# xen_teensy_motherboard_8cv_mki.net
KiCad netlist of a schematic drawn in EAGLE
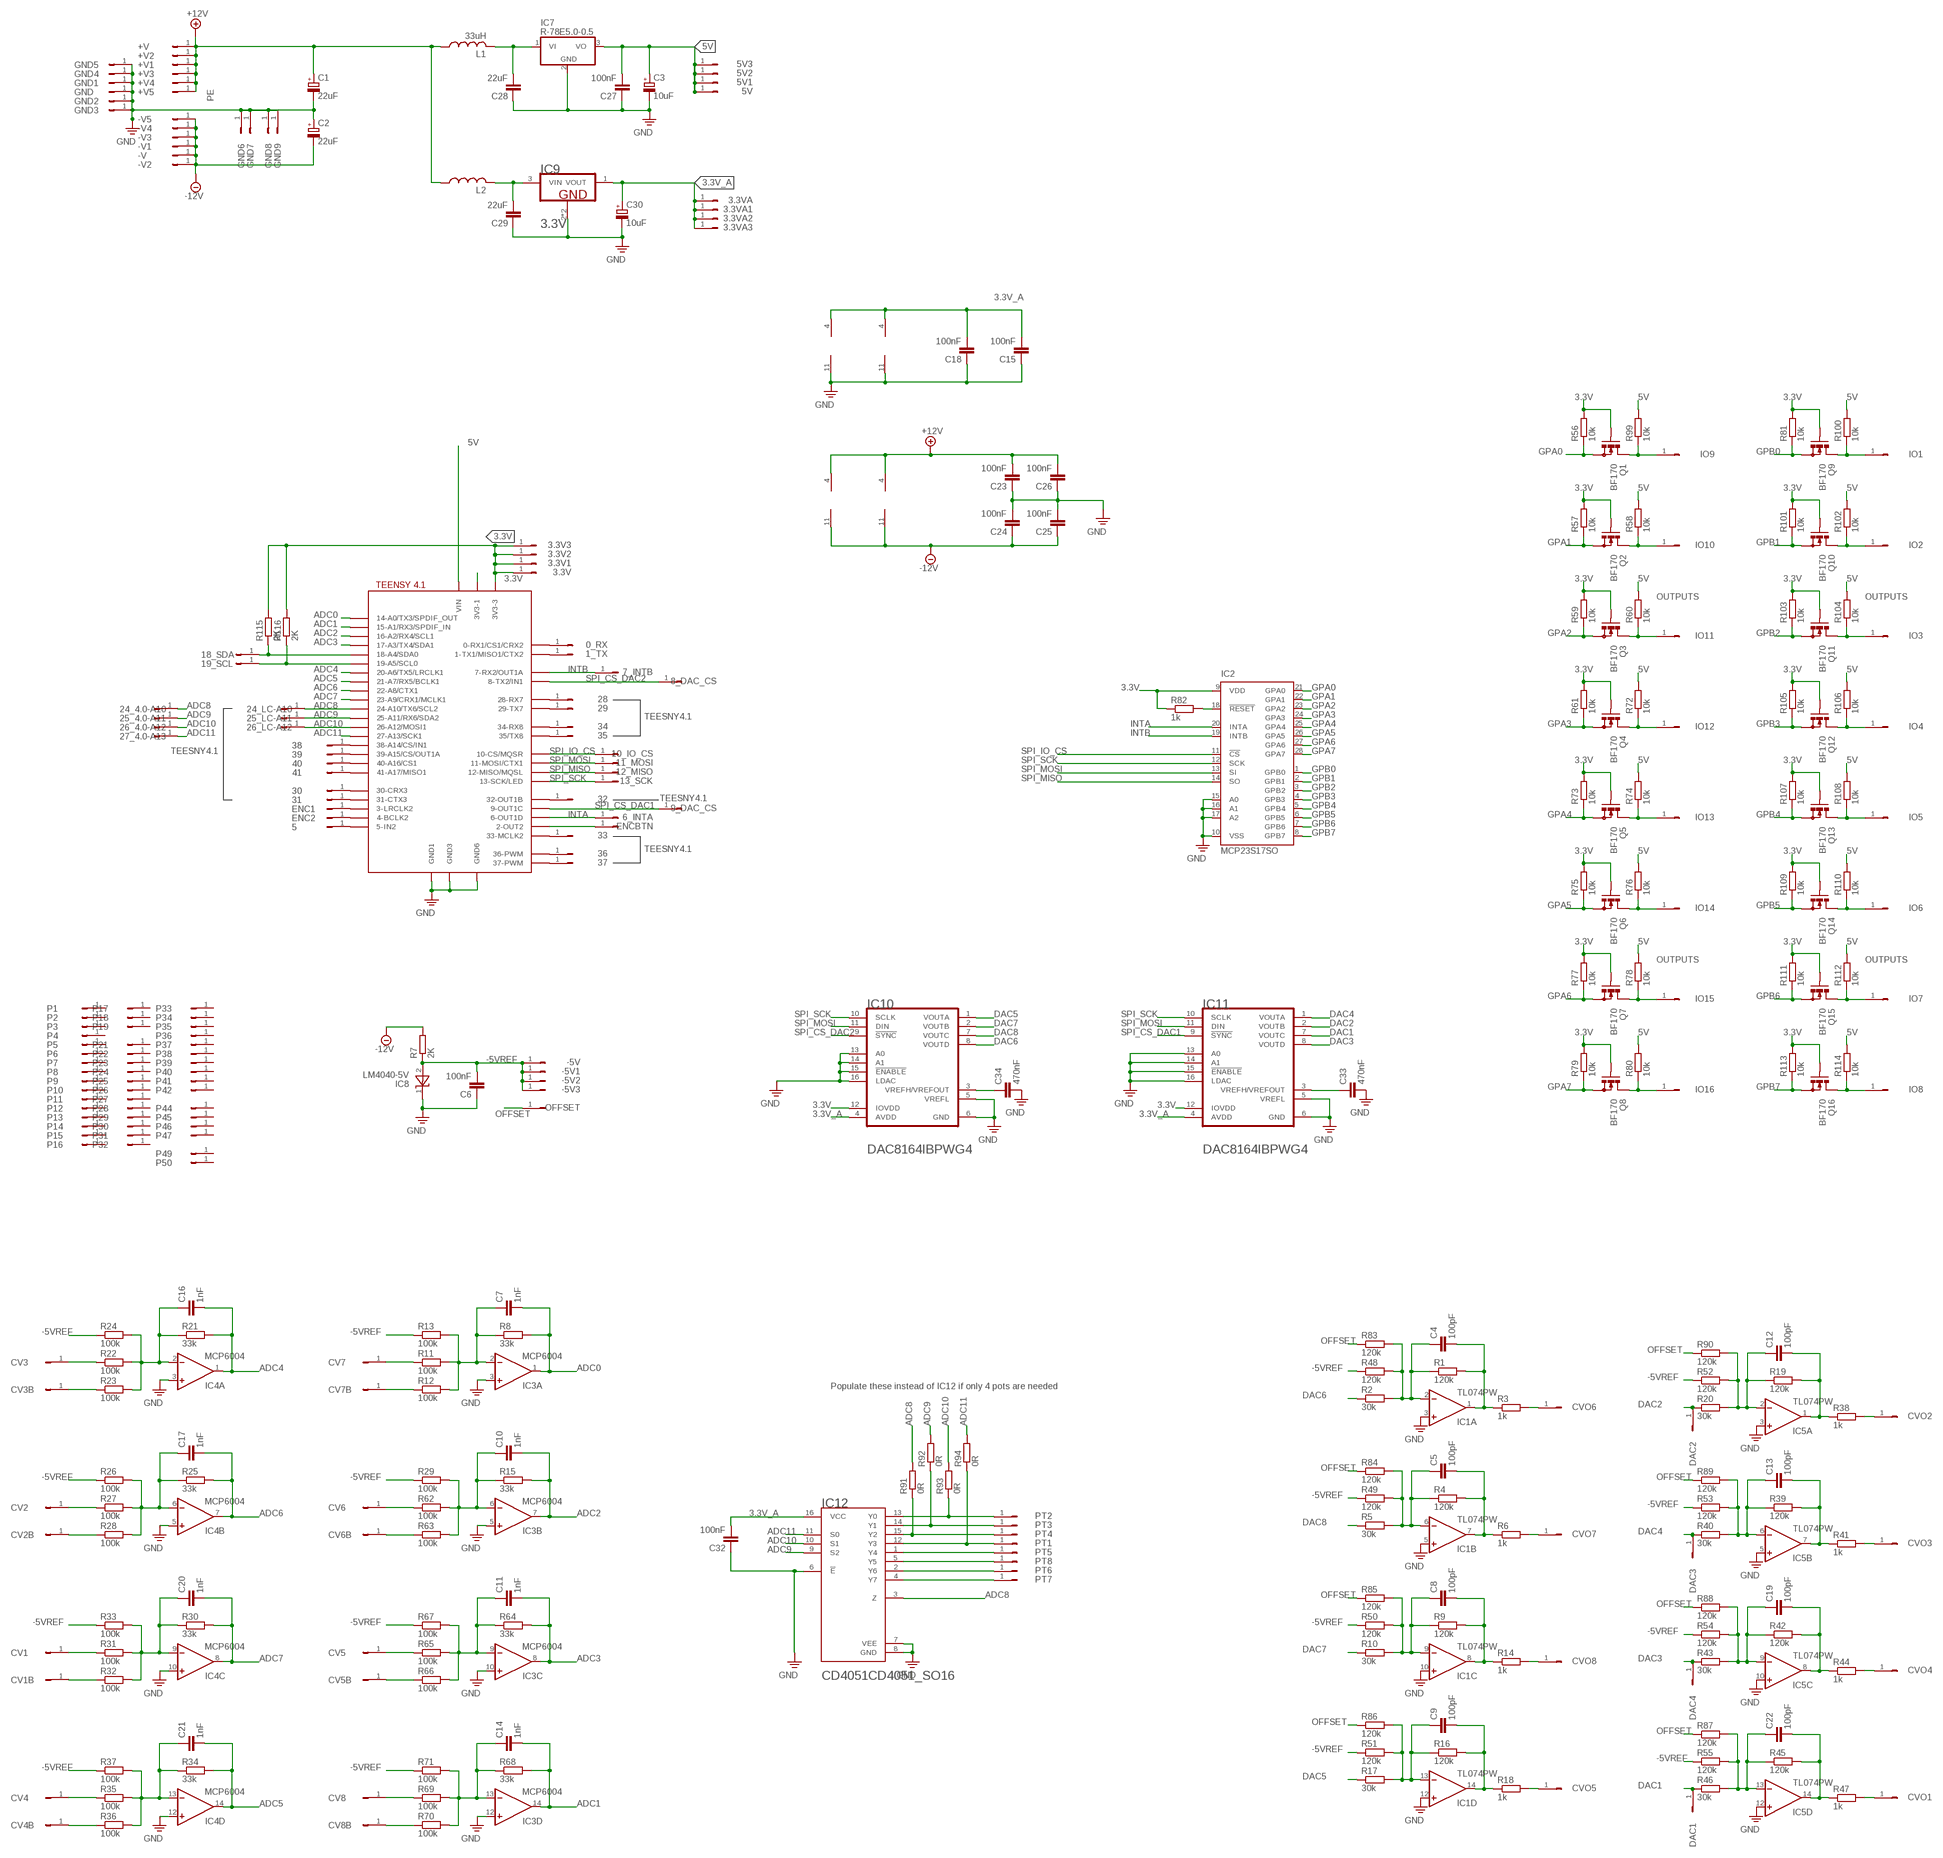
[diagram p0: schematic, sheet 1]

(export (version "E")
  (design (tool "Eeschema 10.0.6"))
  (components
    (comp (ref "+V")
      (value "HEADER/MALE/01")
      (footprint "eagle-import:HEADER_MALE_01")
      (fields (field (name "SPICEPREFIX") "X"))
      (libsource (lib "eagle-import") (part "HEADER/MALE/01"))
    )
    (comp (ref "+V1")
      (value "HEADER/MALE/01")
      (footprint "eagle-import:HEADER_MALE_01")
      (fields (field (name "SPICEPREFIX") "X"))
      (libsource (lib "eagle-import") (part "HEADER/MALE/01"))
    )
    (comp (ref "+V2")
      (value "HEADER/MALE/01")
      (footprint "eagle-import:HEADER_MALE_01")
      (fields (field (name "SPICEPREFIX") "X"))
      (libsource (lib "eagle-import") (part "HEADER/MALE/01"))
    )
    (comp (ref "+V3")
      (value "HEADER/MALE/01")
      (footprint "eagle-import:HEADER_MALE_01")
      (fields (field (name "SPICEPREFIX") "X"))
      (libsource (lib "eagle-import") (part "HEADER/MALE/01"))
    )
    (comp (ref "+V4")
      (value "HEADER/MALE/01")
      (footprint "eagle-import:HEADER_MALE_01")
      (fields (field (name "SPICEPREFIX") "X"))
      (libsource (lib "eagle-import") (part "HEADER/MALE/01"))
    )
    (comp (ref "+V5")
      (value "HEADER/MALE/01")
      (footprint "eagle-import:HEADER_MALE_01")
      (fields (field (name "SPICEPREFIX") "X"))
      (libsource (lib "eagle-import") (part "HEADER/MALE/01"))
    )
    (comp (ref "-5V")
      (value "HEADER/MALE/01")
      (footprint "eagle-import:HEADER_MALE_01")
      (fields (field (name "SPICEPREFIX") "X"))
      (libsource (lib "eagle-import") (part "HEADER/MALE/01"))
    )
    (comp (ref "-5V1")
      (value "HEADER/MALE/01")
      (footprint "eagle-import:HEADER_MALE_01")
      (fields (field (name "SPICEPREFIX") "X"))
      (libsource (lib "eagle-import") (part "HEADER/MALE/01"))
    )
    (comp (ref "-5V2")
      (value "HEADER/MALE/01")
      (footprint "eagle-import:HEADER_MALE_01")
      (fields (field (name "SPICEPREFIX") "X"))
      (libsource (lib "eagle-import") (part "HEADER/MALE/01"))
    )
    (comp (ref "-5V3")
      (value "HEADER/MALE/01")
      (footprint "eagle-import:HEADER_MALE_01")
      (fields (field (name "SPICEPREFIX") "X"))
      (libsource (lib "eagle-import") (part "HEADER/MALE/01"))
    )
    (comp (ref "-V")
      (value "HEADER/MALE/01")
      (footprint "eagle-import:HEADER_MALE_01")
      (fields (field (name "SPICEPREFIX") "X"))
      (libsource (lib "eagle-import") (part "HEADER/MALE/01"))
    )
    (comp (ref "-V1")
      (value "HEADER/MALE/01")
      (footprint "eagle-import:HEADER_MALE_01")
      (fields (field (name "SPICEPREFIX") "X"))
      (libsource (lib "eagle-import") (part "HEADER/MALE/01"))
    )
    (comp (ref "-V2")
      (value "HEADER/MALE/01")
      (footprint "eagle-import:HEADER_MALE_01")
      (fields (field (name "SPICEPREFIX") "X"))
      (libsource (lib "eagle-import") (part "HEADER/MALE/01"))
    )
    (comp (ref "-V3")
      (value "HEADER/MALE/01")
      (footprint "eagle-import:HEADER_MALE_01")
      (fields (field (name "SPICEPREFIX") "X"))
      (libsource (lib "eagle-import") (part "HEADER/MALE/01"))
    )
    (comp (ref "-V4")
      (value "HEADER/MALE/01")
      (footprint "eagle-import:HEADER_MALE_01")
      (fields (field (name "SPICEPREFIX") "X"))
      (libsource (lib "eagle-import") (part "HEADER/MALE/01"))
    )
    (comp (ref "-V5")
      (value "HEADER/MALE/01")
      (footprint "eagle-import:HEADER_MALE_01")
      (fields (field (name "SPICEPREFIX") "X"))
      (libsource (lib "eagle-import") (part "HEADER/MALE/01"))
    )
    (comp (ref "0_RX")
      (value "HEADER/MALE/01")
      (footprint "eagle-import:HEADER_MALE_01")
      (fields (field (name "SPICEPREFIX") "X"))
      (libsource (lib "eagle-import") (part "HEADER/MALE/01"))
    )
    (comp (ref "1_TX")
      (value "HEADER/MALE/01")
      (footprint "eagle-import:HEADER_MALE_01")
      (fields (field (name "SPICEPREFIX") "X"))
      (libsource (lib "eagle-import") (part "HEADER/MALE/01"))
    )
    (comp (ref "3.3V")
      (value "HEADER/MALE/01")
      (footprint "eagle-import:HEADER_MALE_01")
      (fields (field (name "SPICEPREFIX") "X"))
      (libsource (lib "eagle-import") (part "HEADER/MALE/01"))
    )
    (comp (ref "3.3V1")
      (value "HEADER/MALE/01")
      (footprint "eagle-import:HEADER_MALE_01")
      (fields (field (name "SPICEPREFIX") "X"))
      (libsource (lib "eagle-import") (part "HEADER/MALE/01"))
    )
    (comp (ref "3.3V2")
      (value "HEADER/MALE/01")
      (footprint "eagle-import:HEADER_MALE_01")
      (fields (field (name "SPICEPREFIX") "X"))
      (libsource (lib "eagle-import") (part "HEADER/MALE/01"))
    )
    (comp (ref "3.3V3")
      (value "HEADER/MALE/01")
      (footprint "eagle-import:HEADER_MALE_01")
      (fields (field (name "SPICEPREFIX") "X"))
      (libsource (lib "eagle-import") (part "HEADER/MALE/01"))
    )
    (comp (ref "3.3VA")
      (value "HEADER/MALE/01")
      (footprint "eagle-import:HEADER_MALE_01")
      (fields (field (name "SPICEPREFIX") "X"))
      (libsource (lib "eagle-import") (part "HEADER/MALE/01"))
    )
    (comp (ref "3.3VA1")
      (value "HEADER/MALE/01")
      (footprint "eagle-import:HEADER_MALE_01")
      (fields (field (name "SPICEPREFIX") "X"))
      (libsource (lib "eagle-import") (part "HEADER/MALE/01"))
    )
    (comp (ref "3.3VA2")
      (value "HEADER/MALE/01")
      (footprint "eagle-import:HEADER_MALE_01")
      (fields (field (name "SPICEPREFIX") "X"))
      (libsource (lib "eagle-import") (part "HEADER/MALE/01"))
    )
    (comp (ref "3.3VA3")
      (value "HEADER/MALE/01")
      (footprint "eagle-import:HEADER_MALE_01")
      (fields (field (name "SPICEPREFIX") "X"))
      (libsource (lib "eagle-import") (part "HEADER/MALE/01"))
    )
    (comp (ref "5")
      (value "HEADER/MALE/01")
      (footprint "eagle-import:HEADER_MALE_01")
      (fields (field (name "SPICEPREFIX") "X"))
      (libsource (lib "eagle-import") (part "HEADER/MALE/01"))
    )
    (comp (ref "5V")
      (value "HEADER/MALE/01")
      (footprint "eagle-import:HEADER_MALE_01")
      (fields (field (name "SPICEPREFIX") "X"))
      (libsource (lib "eagle-import") (part "HEADER/MALE/01"))
    )
    (comp (ref "5V1")
      (value "HEADER/MALE/01")
      (footprint "eagle-import:HEADER_MALE_01")
      (fields (field (name "SPICEPREFIX") "X"))
      (libsource (lib "eagle-import") (part "HEADER/MALE/01"))
    )
    (comp (ref "5V2")
      (value "HEADER/MALE/01")
      (footprint "eagle-import:HEADER_MALE_01")
      (fields (field (name "SPICEPREFIX") "X"))
      (libsource (lib "eagle-import") (part "HEADER/MALE/01"))
    )
    (comp (ref "5V3")
      (value "HEADER/MALE/01")
      (footprint "eagle-import:HEADER_MALE_01")
      (fields (field (name "SPICEPREFIX") "X"))
      (libsource (lib "eagle-import") (part "HEADER/MALE/01"))
    )
    (comp (ref "6_INTA")
      (value "HEADER/MALE/01")
      (footprint "eagle-import:HEADER_MALE_01")
      (fields (field (name "SPICEPREFIX") "X"))
      (libsource (lib "eagle-import") (part "HEADER/MALE/01"))
    )
    (comp (ref "7_INTB")
      (value "HEADER/MALE/01")
      (footprint "eagle-import:HEADER_MALE_01")
      (fields (field (name "SPICEPREFIX") "X"))
      (libsource (lib "eagle-import") (part "HEADER/MALE/01"))
    )
    (comp (ref "8_DAC_CS")
      (value "HEADER/MALE/01")
      (footprint "eagle-import:HEADER_MALE_01")
      (fields (field (name "SPICEPREFIX") "X"))
      (libsource (lib "eagle-import") (part "HEADER/MALE/01"))
    )
    (comp (ref "9_DAC_CS")
      (value "HEADER/MALE/01")
      (footprint "eagle-import:HEADER_MALE_01")
      (fields (field (name "SPICEPREFIX") "X"))
      (libsource (lib "eagle-import") (part "HEADER/MALE/01"))
    )
    (comp (ref "10_IO_CS")
      (value "HEADER/MALE/01")
      (footprint "eagle-import:HEADER_MALE_01")
      (fields (field (name "SPICEPREFIX") "X"))
      (libsource (lib "eagle-import") (part "HEADER/MALE/01"))
    )
    (comp (ref "11_MOSI")
      (value "HEADER/MALE/01")
      (footprint "eagle-import:HEADER_MALE_01")
      (fields (field (name "SPICEPREFIX") "X"))
      (libsource (lib "eagle-import") (part "HEADER/MALE/01"))
    )
    (comp (ref "12_MISO")
      (value "HEADER/MALE/01")
      (footprint "eagle-import:HEADER_MALE_01")
      (fields (field (name "SPICEPREFIX") "X"))
      (libsource (lib "eagle-import") (part "HEADER/MALE/01"))
    )
    (comp (ref "13_SCK")
      (value "HEADER/MALE/01")
      (footprint "eagle-import:HEADER_MALE_01")
      (fields (field (name "SPICEPREFIX") "X"))
      (libsource (lib "eagle-import") (part "HEADER/MALE/01"))
    )
    (comp (ref "18_SDA")
      (value "HEADER/MALE/01")
      (footprint "eagle-import:HEADER_MALE_01")
      (fields (field (name "SPICEPREFIX") "X"))
      (libsource (lib "eagle-import") (part "HEADER/MALE/01"))
    )
    (comp (ref "19_SCL")
      (value "HEADER/MALE/01")
      (footprint "eagle-import:HEADER_MALE_01")
      (fields (field (name "SPICEPREFIX") "X"))
      (libsource (lib "eagle-import") (part "HEADER/MALE/01"))
    )
    (comp (ref "24_4.0-A10")
      (value "HEADER/MALE/01")
      (footprint "eagle-import:HEADER_MALE_01")
      (fields (field (name "SPICEPREFIX") "X"))
      (libsource (lib "eagle-import") (part "HEADER/MALE/01"))
    )
    (comp (ref "24_LC-A10")
      (value "HEADER/MALE/01")
      (footprint "eagle-import:HEADER_MALE_01")
      (fields (field (name "SPICEPREFIX") "X"))
      (libsource (lib "eagle-import") (part "HEADER/MALE/01"))
    )
    (comp (ref "25_4.0-A11")
      (value "HEADER/MALE/01")
      (footprint "eagle-import:HEADER_MALE_01")
      (fields (field (name "SPICEPREFIX") "X"))
      (libsource (lib "eagle-import") (part "HEADER/MALE/01"))
    )
    (comp (ref "25_LC-A11")
      (value "HEADER/MALE/01")
      (footprint "eagle-import:HEADER_MALE_01")
      (fields (field (name "SPICEPREFIX") "X"))
      (libsource (lib "eagle-import") (part "HEADER/MALE/01"))
    )
    (comp (ref "26_4.0-A12")
      (value "HEADER/MALE/01")
      (footprint "eagle-import:HEADER_MALE_01")
      (fields (field (name "SPICEPREFIX") "X"))
      (libsource (lib "eagle-import") (part "HEADER/MALE/01"))
    )
    (comp (ref "26_LC-A12")
      (value "HEADER/MALE/01")
      (footprint "eagle-import:HEADER_MALE_01")
      (fields (field (name "SPICEPREFIX") "X"))
      (libsource (lib "eagle-import") (part "HEADER/MALE/01"))
    )
    (comp (ref "27_4.0-A13")
      (value "HEADER/MALE/01")
      (footprint "eagle-import:HEADER_MALE_01")
      (fields (field (name "SPICEPREFIX") "X"))
      (libsource (lib "eagle-import") (part "HEADER/MALE/01"))
    )
    (comp (ref "28")
      (value "HEADER/MALE/01")
      (footprint "eagle-import:HEADER_MALE_01")
      (fields (field (name "SPICEPREFIX") "X"))
      (libsource (lib "eagle-import") (part "HEADER/MALE/01"))
    )
    (comp (ref "29")
      (value "HEADER/MALE/01")
      (footprint "eagle-import:HEADER_MALE_01")
      (fields (field (name "SPICEPREFIX") "X"))
      (libsource (lib "eagle-import") (part "HEADER/MALE/01"))
    )
    (comp (ref "30")
      (value "HEADER/MALE/01")
      (footprint "eagle-import:HEADER_MALE_01")
      (fields (field (name "SPICEPREFIX") "X"))
      (libsource (lib "eagle-import") (part "HEADER/MALE/01"))
    )
    (comp (ref "31")
      (value "HEADER/MALE/01")
      (footprint "eagle-import:HEADER_MALE_01")
      (fields (field (name "SPICEPREFIX") "X"))
      (libsource (lib "eagle-import") (part "HEADER/MALE/01"))
    )
    (comp (ref "32")
      (value "HEADER/MALE/01")
      (footprint "eagle-import:HEADER_MALE_01")
      (fields (field (name "SPICEPREFIX") "X"))
      (libsource (lib "eagle-import") (part "HEADER/MALE/01"))
    )
    (comp (ref "33")
      (value "HEADER/MALE/01")
      (footprint "eagle-import:HEADER_MALE_01")
      (fields (field (name "SPICEPREFIX") "X"))
      (libsource (lib "eagle-import") (part "HEADER/MALE/01"))
    )
    (comp (ref "34")
      (value "HEADER/MALE/01")
      (footprint "eagle-import:HEADER_MALE_01")
      (fields (field (name "SPICEPREFIX") "X"))
      (libsource (lib "eagle-import") (part "HEADER/MALE/01"))
    )
    (comp (ref "35")
      (value "HEADER/MALE/01")
      (footprint "eagle-import:HEADER_MALE_01")
      (fields (field (name "SPICEPREFIX") "X"))
      (libsource (lib "eagle-import") (part "HEADER/MALE/01"))
    )
    (comp (ref "36")
      (value "HEADER/MALE/01")
      (footprint "eagle-import:HEADER_MALE_01")
      (fields (field (name "SPICEPREFIX") "X"))
      (libsource (lib "eagle-import") (part "HEADER/MALE/01"))
    )
    (comp (ref "37")
      (value "HEADER/MALE/01")
      (footprint "eagle-import:HEADER_MALE_01")
      (fields (field (name "SPICEPREFIX") "X"))
      (libsource (lib "eagle-import") (part "HEADER/MALE/01"))
    )
    (comp (ref "38")
      (value "HEADER/MALE/01")
      (footprint "eagle-import:HEADER_MALE_01")
      (fields (field (name "SPICEPREFIX") "X"))
      (libsource (lib "eagle-import") (part "HEADER/MALE/01"))
    )
    (comp (ref "39")
      (value "HEADER/MALE/01")
      (footprint "eagle-import:HEADER_MALE_01")
      (fields (field (name "SPICEPREFIX") "X"))
      (libsource (lib "eagle-import") (part "HEADER/MALE/01"))
    )
    (comp (ref "40")
      (value "HEADER/MALE/01")
      (footprint "eagle-import:HEADER_MALE_01")
      (fields (field (name "SPICEPREFIX") "X"))
      (libsource (lib "eagle-import") (part "HEADER/MALE/01"))
    )
    (comp (ref "41")
      (value "HEADER/MALE/01")
      (footprint "eagle-import:HEADER_MALE_01")
      (fields (field (name "SPICEPREFIX") "X"))
      (libsource (lib "eagle-import") (part "HEADER/MALE/01"))
    )
    (comp (ref "C1")
      (value "22uF")
      (footprint "eagle-import:SV-C")
      (fields (field (name "SPICEPREFIX") "C"))
      (libsource (lib "eagle-import") (part "CAPACITOR/POLARIZEDSMDC"))
    )
    (comp (ref "C2")
      (value "22uF")
      (footprint "eagle-import:SV-C")
      (fields (field (name "SPICEPREFIX") "C"))
      (libsource (lib "eagle-import") (part "CAPACITOR/POLARIZEDSMDC"))
    )
    (comp (ref "C3")
      (value "10uF")
      (footprint "eagle-import:SV-B")
      (fields (field (name "SPICEPREFIX") "C"))
      (libsource (lib "eagle-import") (part "CAPACITOR/POLARIZEDSMDB"))
    )
    (comp (ref "C4")
      (value "100pF")
      (footprint "eagle-import:C0603")
      (libsource (lib "eagle-import") (part "CAPACITORC0603"))
    )
    (comp (ref "C5")
      (value "100pF")
      (footprint "eagle-import:C0603")
      (libsource (lib "eagle-import") (part "CAPACITORC0603"))
    )
    (comp (ref "C6")
      (value "100nF")
      (footprint "eagle-import:C0603")
      (libsource (lib "eagle-import") (part "CAPACITORC0603"))
    )
    (comp (ref "C7")
      (value "1nF")
      (footprint "eagle-import:C0603")
      (libsource (lib "eagle-import") (part "CAPACITORC0603"))
    )
    (comp (ref "C8")
      (value "100pF")
      (footprint "eagle-import:C0603")
      (libsource (lib "eagle-import") (part "CAPACITORC0603"))
    )
    (comp (ref "C9")
      (value "100pF")
      (footprint "eagle-import:C0603")
      (libsource (lib "eagle-import") (part "CAPACITORC0603"))
    )
    (comp (ref "C10")
      (value "1nF")
      (footprint "eagle-import:C0603")
      (libsource (lib "eagle-import") (part "CAPACITORC0603"))
    )
    (comp (ref "C11")
      (value "1nF")
      (footprint "eagle-import:C0603")
      (libsource (lib "eagle-import") (part "CAPACITORC0603"))
    )
    (comp (ref "C12")
      (value "100pF")
      (footprint "eagle-import:C0603")
      (libsource (lib "eagle-import") (part "CAPACITORC0603"))
    )
    (comp (ref "C13")
      (value "100pF")
      (footprint "eagle-import:C0603")
      (libsource (lib "eagle-import") (part "CAPACITORC0603"))
    )
    (comp (ref "C14")
      (value "1nF")
      (footprint "eagle-import:C0603")
      (libsource (lib "eagle-import") (part "CAPACITORC0603"))
    )
    (comp (ref "C15")
      (value "100nF")
      (footprint "eagle-import:C0603")
      (libsource (lib "eagle-import") (part "CAPACITORC0603"))
    )
    (comp (ref "C16")
      (value "1nF")
      (footprint "eagle-import:C0603")
      (libsource (lib "eagle-import") (part "CAPACITORC0603"))
    )
    (comp (ref "C17")
      (value "1nF")
      (footprint "eagle-import:C0603")
      (libsource (lib "eagle-import") (part "CAPACITORC0603"))
    )
    (comp (ref "C18")
      (value "100nF")
      (footprint "eagle-import:C0603")
      (libsource (lib "eagle-import") (part "CAPACITORC0603"))
    )
    (comp (ref "C19")
      (value "100pF")
      (footprint "eagle-import:C0603")
      (libsource (lib "eagle-import") (part "CAPACITORC0603"))
    )
    (comp (ref "C20")
      (value "1nF")
      (footprint "eagle-import:C0603")
      (libsource (lib "eagle-import") (part "CAPACITORC0603"))
    )
    (comp (ref "C21")
      (value "1nF")
      (footprint "eagle-import:C0603")
      (libsource (lib "eagle-import") (part "CAPACITORC0603"))
    )
    (comp (ref "C22")
      (value "100pF")
      (footprint "eagle-import:C0603")
      (libsource (lib "eagle-import") (part "CAPACITORC0603"))
    )
    (comp (ref "C23")
      (value "100nF")
      (footprint "eagle-import:C0603")
      (libsource (lib "eagle-import") (part "CAPACITORC0603"))
    )
    (comp (ref "C24")
      (value "100nF")
      (footprint "eagle-import:C0603")
      (libsource (lib "eagle-import") (part "CAPACITORC0603"))
    )
    (comp (ref "C25")
      (value "100nF")
      (footprint "eagle-import:C0603")
      (libsource (lib "eagle-import") (part "CAPACITORC0603"))
    )
    (comp (ref "C26")
      (value "100nF")
      (footprint "eagle-import:C0603")
      (libsource (lib "eagle-import") (part "CAPACITORC0603"))
    )
    (comp (ref "C27")
      (value "100nF")
      (footprint "eagle-import:C0603")
      (libsource (lib "eagle-import") (part "CAPACITORC0603"))
    )
    (comp (ref "C28")
      (value "22uF")
      (footprint "eagle-import:C0805")
      (libsource (lib "eagle-import") (part "CAPACITORC0805"))
    )
    (comp (ref "C29")
      (value "22uF")
      (footprint "eagle-import:C0805")
      (libsource (lib "eagle-import") (part "CAPACITORC0805"))
    )
    (comp (ref "C30")
      (value "10uF")
      (footprint "eagle-import:SV-B")
      (fields (field (name "SPICEPREFIX") "C"))
      (libsource (lib "eagle-import") (part "CAPACITOR/POLARIZEDSMDB"))
    )
    (comp (ref "C32")
      (value "100nF")
      (footprint "eagle-import:C0603")
      (libsource (lib "eagle-import") (part "CAPACITORC0603"))
    )
    (comp (ref "C33")
      (value "470nF")
      (footprint "eagle-import:C0603")
      (libsource (lib "eagle-import") (part "CAPACITORC0603"))
    )
    (comp (ref "C34")
      (value "470nF")
      (footprint "eagle-import:C0603")
      (libsource (lib "eagle-import") (part "CAPACITORC0603"))
    )
    (comp (ref "CV1")
      (value "HEADER/MALE/01")
      (footprint "eagle-import:HEADER_MALE_01")
      (fields (field (name "SPICEPREFIX") "X"))
      (libsource (lib "eagle-import") (part "HEADER/MALE/01"))
    )
    (comp (ref "CV1B")
      (value "HEADER/MALE/01")
      (footprint "eagle-import:HEADER_MALE_01")
      (fields (field (name "SPICEPREFIX") "X"))
      (libsource (lib "eagle-import") (part "HEADER/MALE/01"))
    )
    (comp (ref "CV2")
      (value "HEADER/MALE/01")
      (footprint "eagle-import:HEADER_MALE_01")
      (fields (field (name "SPICEPREFIX") "X"))
      (libsource (lib "eagle-import") (part "HEADER/MALE/01"))
    )
    (comp (ref "CV2B")
      (value "HEADER/MALE/01")
      (footprint "eagle-import:HEADER_MALE_01")
      (fields (field (name "SPICEPREFIX") "X"))
      (libsource (lib "eagle-import") (part "HEADER/MALE/01"))
    )
    (comp (ref "CV3")
      (value "HEADER/MALE/01")
      (footprint "eagle-import:HEADER_MALE_01")
      (fields (field (name "SPICEPREFIX") "X"))
      (libsource (lib "eagle-import") (part "HEADER/MALE/01"))
    )
    (comp (ref "CV3B")
      (value "HEADER/MALE/01")
      (footprint "eagle-import:HEADER_MALE_01")
      (fields (field (name "SPICEPREFIX") "X"))
      (libsource (lib "eagle-import") (part "HEADER/MALE/01"))
    )
    (comp (ref "CV4")
      (value "HEADER/MALE/01")
      (footprint "eagle-import:HEADER_MALE_01")
      (fields (field (name "SPICEPREFIX") "X"))
      (libsource (lib "eagle-import") (part "HEADER/MALE/01"))
    )
    (comp (ref "CV4B")
      (value "HEADER/MALE/01")
      (footprint "eagle-import:HEADER_MALE_01")
      (fields (field (name "SPICEPREFIX") "X"))
      (libsource (lib "eagle-import") (part "HEADER/MALE/01"))
    )
    (comp (ref "CV5")
      (value "HEADER/MALE/01")
      (footprint "eagle-import:HEADER_MALE_01")
      (fields (field (name "SPICEPREFIX") "X"))
      (libsource (lib "eagle-import") (part "HEADER/MALE/01"))
    )
    (comp (ref "CV5B")
      (value "HEADER/MALE/01")
      (footprint "eagle-import:HEADER_MALE_01")
      (fields (field (name "SPICEPREFIX") "X"))
      (libsource (lib "eagle-import") (part "HEADER/MALE/01"))
    )
    (comp (ref "CV6")
      (value "HEADER/MALE/01")
      (footprint "eagle-import:HEADER_MALE_01")
      (fields (field (name "SPICEPREFIX") "X"))
      (libsource (lib "eagle-import") (part "HEADER/MALE/01"))
    )
    (comp (ref "CV6B")
      (value "HEADER/MALE/01")
      (footprint "eagle-import:HEADER_MALE_01")
      (fields (field (name "SPICEPREFIX") "X"))
      (libsource (lib "eagle-import") (part "HEADER/MALE/01"))
    )
    (comp (ref "CV7")
      (value "HEADER/MALE/01")
      (footprint "eagle-import:HEADER_MALE_01")
      (fields (field (name "SPICEPREFIX") "X"))
      (libsource (lib "eagle-import") (part "HEADER/MALE/01"))
    )
    (comp (ref "CV7B")
      (value "HEADER/MALE/01")
      (footprint "eagle-import:HEADER_MALE_01")
      (fields (field (name "SPICEPREFIX") "X"))
      (libsource (lib "eagle-import") (part "HEADER/MALE/01"))
    )
    (comp (ref "CV8")
      (value "HEADER/MALE/01")
      (footprint "eagle-import:HEADER_MALE_01")
      (fields (field (name "SPICEPREFIX") "X"))
      (libsource (lib "eagle-import") (part "HEADER/MALE/01"))
    )
    (comp (ref "CV8B")
      (value "HEADER/MALE/01")
      (footprint "eagle-import:HEADER_MALE_01")
      (fields (field (name "SPICEPREFIX") "X"))
      (libsource (lib "eagle-import") (part "HEADER/MALE/01"))
    )
    (comp (ref "CVO1")
      (value "HEADER/MALE/01")
      (footprint "eagle-import:HEADER_MALE_01")
      (fields (field (name "SPICEPREFIX") "X"))
      (libsource (lib "eagle-import") (part "HEADER/MALE/01"))
    )
    (comp (ref "CVO2")
      (value "HEADER/MALE/01")
      (footprint "eagle-import:HEADER_MALE_01")
      (fields (field (name "SPICEPREFIX") "X"))
      (libsource (lib "eagle-import") (part "HEADER/MALE/01"))
    )
    (comp (ref "CVO3")
      (value "HEADER/MALE/01")
      (footprint "eagle-import:HEADER_MALE_01")
      (fields (field (name "SPICEPREFIX") "X"))
      (libsource (lib "eagle-import") (part "HEADER/MALE/01"))
    )
    (comp (ref "CVO4")
      (value "HEADER/MALE/01")
      (footprint "eagle-import:HEADER_MALE_01")
      (fields (field (name "SPICEPREFIX") "X"))
      (libsource (lib "eagle-import") (part "HEADER/MALE/01"))
    )
    (comp (ref "CVO5")
      (value "HEADER/MALE/01")
      (footprint "eagle-import:HEADER_MALE_01")
      (fields (field (name "SPICEPREFIX") "X"))
      (libsource (lib "eagle-import") (part "HEADER/MALE/01"))
    )
    (comp (ref "CVO6")
      (value "HEADER/MALE/01")
      (footprint "eagle-import:HEADER_MALE_01")
      (fields (field (name "SPICEPREFIX") "X"))
      (libsource (lib "eagle-import") (part "HEADER/MALE/01"))
    )
    (comp (ref "CVO7")
      (value "HEADER/MALE/01")
      (footprint "eagle-import:HEADER_MALE_01")
      (fields (field (name "SPICEPREFIX") "X"))
      (libsource (lib "eagle-import") (part "HEADER/MALE/01"))
    )
    (comp (ref "CVO8")
      (value "HEADER/MALE/01")
      (footprint "eagle-import:HEADER_MALE_01")
      (fields (field (name "SPICEPREFIX") "X"))
      (libsource (lib "eagle-import") (part "HEADER/MALE/01"))
    )
    (comp (ref "DAC1")
      (value "HEADER/MALE/01")
      (footprint "eagle-import:HEADER_MALE_01")
      (fields (field (name "SPICEPREFIX") "X"))
      (libsource (lib "eagle-import") (part "HEADER/MALE/01"))
    )
    (comp (ref "DAC2")
      (value "HEADER/MALE/01")
      (footprint "eagle-import:HEADER_MALE_01")
      (fields (field (name "SPICEPREFIX") "X"))
      (libsource (lib "eagle-import") (part "HEADER/MALE/01"))
    )
    (comp (ref "DAC3")
      (value "HEADER/MALE/01")
      (footprint "eagle-import:HEADER_MALE_01")
      (fields (field (name "SPICEPREFIX") "X"))
      (libsource (lib "eagle-import") (part "HEADER/MALE/01"))
    )
    (comp (ref "DAC4")
      (value "HEADER/MALE/01")
      (footprint "eagle-import:HEADER_MALE_01")
      (fields (field (name "SPICEPREFIX") "X"))
      (libsource (lib "eagle-import") (part "HEADER/MALE/01"))
    )
    (comp (ref "ENC1")
      (value "HEADER/MALE/01")
      (footprint "eagle-import:HEADER_MALE_01")
      (fields (field (name "SPICEPREFIX") "X"))
      (libsource (lib "eagle-import") (part "HEADER/MALE/01"))
    )
    (comp (ref "ENC2")
      (value "HEADER/MALE/01")
      (footprint "eagle-import:HEADER_MALE_01")
      (fields (field (name "SPICEPREFIX") "X"))
      (libsource (lib "eagle-import") (part "HEADER/MALE/01"))
    )
    (comp (ref "ENCBTN")
      (value "HEADER/MALE/01")
      (footprint "eagle-import:HEADER_MALE_01")
      (fields (field (name "SPICEPREFIX") "X"))
      (libsource (lib "eagle-import") (part "HEADER/MALE/01"))
    )
    (comp (ref "GND")
      (value "HEADER/MALE/01")
      (footprint "eagle-import:HEADER_MALE_01")
      (fields (field (name "SPICEPREFIX") "X"))
      (libsource (lib "eagle-import") (part "HEADER/MALE/01"))
    )
    (comp (ref "GND1")
      (value "HEADER/MALE/01")
      (footprint "eagle-import:HEADER_MALE_01")
      (fields (field (name "SPICEPREFIX") "X"))
      (libsource (lib "eagle-import") (part "HEADER/MALE/01"))
    )
    (comp (ref "GND2")
      (value "HEADER/MALE/01")
      (footprint "eagle-import:HEADER_MALE_01")
      (fields (field (name "SPICEPREFIX") "X"))
      (libsource (lib "eagle-import") (part "HEADER/MALE/01"))
    )
    (comp (ref "GND3")
      (value "HEADER/MALE/01")
      (footprint "eagle-import:HEADER_MALE_01")
      (fields (field (name "SPICEPREFIX") "X"))
      (libsource (lib "eagle-import") (part "HEADER/MALE/01"))
    )
    (comp (ref "GND4")
      (value "HEADER/MALE/01")
      (footprint "eagle-import:HEADER_MALE_01")
      (fields (field (name "SPICEPREFIX") "X"))
      (libsource (lib "eagle-import") (part "HEADER/MALE/01"))
    )
    (comp (ref "GND5")
      (value "HEADER/MALE/01")
      (footprint "eagle-import:HEADER_MALE_01")
      (fields (field (name "SPICEPREFIX") "X"))
      (libsource (lib "eagle-import") (part "HEADER/MALE/01"))
    )
    (comp (ref "GND6")
      (value "HEADER/MALE/01")
      (footprint "eagle-import:HEADER_MALE_01")
      (fields (field (name "SPICEPREFIX") "X"))
      (libsource (lib "eagle-import") (part "HEADER/MALE/01"))
    )
    (comp (ref "GND7")
      (value "HEADER/MALE/01")
      (footprint "eagle-import:HEADER_MALE_01")
      (fields (field (name "SPICEPREFIX") "X"))
      (libsource (lib "eagle-import") (part "HEADER/MALE/01"))
    )
    (comp (ref "GND8")
      (value "HEADER/MALE/01")
      (footprint "eagle-import:HEADER_MALE_01")
      (fields (field (name "SPICEPREFIX") "X"))
      (libsource (lib "eagle-import") (part "HEADER/MALE/01"))
    )
    (comp (ref "GND9")
      (value "HEADER/MALE/01")
      (footprint "eagle-import:HEADER_MALE_01")
      (fields (field (name "SPICEPREFIX") "X"))
      (libsource (lib "eagle-import") (part "HEADER/MALE/01"))
    )
    (comp (ref "IC1")
      (value "TL074PW")
      (footprint "eagle-import:TSSOP14")
      (libsource (lib "eagle-import") (part "TL074PW"))
    )
    (comp (ref "IC2")
      (value "MCP23S17SO")
      (footprint "eagle-import:SO28W")
      (fields (field (name "MF") "MICROCHIP") (field (name "MPN") "MCP23S17-E/SO"))
      (libsource (lib "eagle-import") (part "MCP23S17SO"))
    )
    (comp (ref "IC3")
      (value "MCP6004")
      (footprint "eagle-import:TSSOP14")
      (libsource (lib "eagle-import") (part "TL074PW"))
    )
    (comp (ref "IC4")
      (value "MCP6004")
      (footprint "eagle-import:TSSOP14")
      (libsource (lib "eagle-import") (part "TL074PW"))
    )
    (comp (ref "IC5")
      (value "TL074PW")
      (footprint "eagle-import:TSSOP14")
      (libsource (lib "eagle-import") (part "TL074PW"))
    )
    (comp (ref "IC6")
      (value "TEENSY41-OUTER")
      (footprint "eagle-import:TENNSY41-OUTER")
      (libsource (lib "eagle-import") (part "TEENSY41-OUTER"))
    )
    (comp (ref "IC7")
      (value "R-78E5.0-0.5")
      (footprint "eagle-import:WE78")
      (libsource (lib "eagle-import") (part "WE173950378"))
    )
    (comp (ref "IC8")
      (value "LM4040-5V")
      (footprint "eagle-import:SOT-23")
      (libsource (lib "eagle-import") (part "LM4040CYM3-2.5"))
    )
    (comp (ref "IC9")
      (value "3.3V")
      (footprint "eagle-import:LD2981-SOT89")
      (fields (field (name "MF") "STMicroelectronics") (field (name "MPN") "LD2981CU33TR"))
      (libsource (lib "eagle-import") (part "LD2981LD2981-SOT89"))
    )
    (comp (ref "IC10")
      (value "TEXAS_INSTRUMENTS_DAC8164IBPWG4TEXAS_INSTRUMENTS_DAC8164IBPWG4_0_1")
      (footprint "eagle-import:TEXAS_INSTRUMENTS_DAC8164IBPWG4_1")
      (fields (field (name "MF") "Texas Instruments") (field (name "MPN") "DAC8164IBPWG4"))
      (libsource (lib "eagle-import") (part "TEXAS_INSTRUMENTS_DAC8164IBPWG4TEXAS_INSTRUMENTS_DAC8164IBPWG4_0_1"))
    )
    (comp (ref "IC11")
      (value "TEXAS_INSTRUMENTS_DAC8164IBPWG4TEXAS_INSTRUMENTS_DAC8164IBPWG4_0_1")
      (footprint "eagle-import:TEXAS_INSTRUMENTS_DAC8164IBPWG4_1")
      (fields (field (name "MF") "Texas Instruments") (field (name "MPN") "DAC8164IBPWG4"))
      (libsource (lib "eagle-import") (part "TEXAS_INSTRUMENTS_DAC8164IBPWG4TEXAS_INSTRUMENTS_DAC8164IBPWG4_0_1"))
    )
    (comp (ref "IC12")
      (value "CD4051CD4051_SO16")
      (footprint "eagle-import:SO16")
      (libsource (lib "eagle-import") (part "CD4051CD4051_SO16"))
    )
    (comp (ref "IO1")
      (value "HEADER/MALE/01")
      (footprint "eagle-import:HEADER_MALE_01")
      (fields (field (name "SPICEPREFIX") "X"))
      (libsource (lib "eagle-import") (part "HEADER/MALE/01"))
    )
    (comp (ref "IO2")
      (value "HEADER/MALE/01")
      (footprint "eagle-import:HEADER_MALE_01")
      (fields (field (name "SPICEPREFIX") "X"))
      (libsource (lib "eagle-import") (part "HEADER/MALE/01"))
    )
    (comp (ref "IO3")
      (value "HEADER/MALE/01")
      (footprint "eagle-import:HEADER_MALE_01")
      (fields (field (name "SPICEPREFIX") "X"))
      (libsource (lib "eagle-import") (part "HEADER/MALE/01"))
    )
    (comp (ref "IO4")
      (value "HEADER/MALE/01")
      (footprint "eagle-import:HEADER_MALE_01")
      (fields (field (name "SPICEPREFIX") "X"))
      (libsource (lib "eagle-import") (part "HEADER/MALE/01"))
    )
    (comp (ref "IO5")
      (value "HEADER/MALE/01")
      (footprint "eagle-import:HEADER_MALE_01")
      (fields (field (name "SPICEPREFIX") "X"))
      (libsource (lib "eagle-import") (part "HEADER/MALE/01"))
    )
    (comp (ref "IO6")
      (value "HEADER/MALE/01")
      (footprint "eagle-import:HEADER_MALE_01")
      (fields (field (name "SPICEPREFIX") "X"))
      (libsource (lib "eagle-import") (part "HEADER/MALE/01"))
    )
    (comp (ref "IO7")
      (value "HEADER/MALE/01")
      (footprint "eagle-import:HEADER_MALE_01")
      (fields (field (name "SPICEPREFIX") "X"))
      (libsource (lib "eagle-import") (part "HEADER/MALE/01"))
    )
    (comp (ref "IO8")
      (value "HEADER/MALE/01")
      (footprint "eagle-import:HEADER_MALE_01")
      (fields (field (name "SPICEPREFIX") "X"))
      (libsource (lib "eagle-import") (part "HEADER/MALE/01"))
    )
    (comp (ref "IO9")
      (value "HEADER/MALE/01")
      (footprint "eagle-import:HEADER_MALE_01")
      (fields (field (name "SPICEPREFIX") "X"))
      (libsource (lib "eagle-import") (part "HEADER/MALE/01"))
    )
    (comp (ref "IO10")
      (value "HEADER/MALE/01")
      (footprint "eagle-import:HEADER_MALE_01")
      (fields (field (name "SPICEPREFIX") "X"))
      (libsource (lib "eagle-import") (part "HEADER/MALE/01"))
    )
    (comp (ref "IO11")
      (value "HEADER/MALE/01")
      (footprint "eagle-import:HEADER_MALE_01")
      (fields (field (name "SPICEPREFIX") "X"))
      (libsource (lib "eagle-import") (part "HEADER/MALE/01"))
    )
    (comp (ref "IO12")
      (value "HEADER/MALE/01")
      (footprint "eagle-import:HEADER_MALE_01")
      (fields (field (name "SPICEPREFIX") "X"))
      (libsource (lib "eagle-import") (part "HEADER/MALE/01"))
    )
    (comp (ref "IO13")
      (value "HEADER/MALE/01")
      (footprint "eagle-import:HEADER_MALE_01")
      (fields (field (name "SPICEPREFIX") "X"))
      (libsource (lib "eagle-import") (part "HEADER/MALE/01"))
    )
    (comp (ref "IO14")
      (value "HEADER/MALE/01")
      (footprint "eagle-import:HEADER_MALE_01")
      (fields (field (name "SPICEPREFIX") "X"))
      (libsource (lib "eagle-import") (part "HEADER/MALE/01"))
    )
    (comp (ref "IO15")
      (value "HEADER/MALE/01")
      (footprint "eagle-import:HEADER_MALE_01")
      (fields (field (name "SPICEPREFIX") "X"))
      (libsource (lib "eagle-import") (part "HEADER/MALE/01"))
    )
    (comp (ref "IO16")
      (value "HEADER/MALE/01")
      (footprint "eagle-import:HEADER_MALE_01")
      (fields (field (name "SPICEPREFIX") "X"))
      (libsource (lib "eagle-import") (part "HEADER/MALE/01"))
    )
    (comp (ref "L1")
      (value "33uH")
      (footprint "eagle-import:L2012C")
      (libsource (lib "eagle-import") (part "INDUCTORL2012C"))
    )
    (comp (ref "L2")
      (value "INDUCTORL0603")
      (footprint "eagle-import:R0603")
      (libsource (lib "eagle-import") (part "INDUCTORL0603"))
    )
    (comp (ref "OFFSET")
      (value "HEADER/MALE/01")
      (footprint "eagle-import:HEADER_MALE_01")
      (fields (field (name "SPICEPREFIX") "X"))
      (libsource (lib "eagle-import") (part "HEADER/MALE/01"))
    )
    (comp (ref "P1")
      (value "HEADER/MALE/01NOBORDER")
      (footprint "eagle-import:HEADER_MALE_01_NOBORDER")
      (fields (field (name "SPICEPREFIX") "X"))
      (libsource (lib "eagle-import") (part "HEADER/MALE/01NOBORDER"))
    )
    (comp (ref "P2")
      (value "HEADER/MALE/01NOBORDER")
      (footprint "eagle-import:HEADER_MALE_01_NOBORDER")
      (fields (field (name "SPICEPREFIX") "X"))
      (libsource (lib "eagle-import") (part "HEADER/MALE/01NOBORDER"))
    )
    (comp (ref "P3")
      (value "HEADER/MALE/01NOBORDER")
      (footprint "eagle-import:HEADER_MALE_01_NOBORDER")
      (fields (field (name "SPICEPREFIX") "X"))
      (libsource (lib "eagle-import") (part "HEADER/MALE/01NOBORDER"))
    )
    (comp (ref "P4")
      (value "HEADER/MALE/01NOBORDER")
      (footprint "eagle-import:HEADER_MALE_01_NOBORDER")
      (fields (field (name "SPICEPREFIX") "X"))
      (libsource (lib "eagle-import") (part "HEADER/MALE/01NOBORDER"))
    )
    (comp (ref "P5")
      (value "HEADER/MALE/01NOBORDER")
      (footprint "eagle-import:HEADER_MALE_01_NOBORDER")
      (fields (field (name "SPICEPREFIX") "X"))
      (libsource (lib "eagle-import") (part "HEADER/MALE/01NOBORDER"))
    )
    (comp (ref "P6")
      (value "HEADER/MALE/01NOBORDER")
      (footprint "eagle-import:HEADER_MALE_01_NOBORDER")
      (fields (field (name "SPICEPREFIX") "X"))
      (libsource (lib "eagle-import") (part "HEADER/MALE/01NOBORDER"))
    )
    (comp (ref "P7")
      (value "HEADER/MALE/01NOBORDER")
      (footprint "eagle-import:HEADER_MALE_01_NOBORDER")
      (fields (field (name "SPICEPREFIX") "X"))
      (libsource (lib "eagle-import") (part "HEADER/MALE/01NOBORDER"))
    )
    (comp (ref "P8")
      (value "HEADER/MALE/01NOBORDER")
      (footprint "eagle-import:HEADER_MALE_01_NOBORDER")
      (fields (field (name "SPICEPREFIX") "X"))
      (libsource (lib "eagle-import") (part "HEADER/MALE/01NOBORDER"))
    )
    (comp (ref "P9")
      (value "HEADER/MALE/01NOBORDER")
      (footprint "eagle-import:HEADER_MALE_01_NOBORDER")
      (fields (field (name "SPICEPREFIX") "X"))
      (libsource (lib "eagle-import") (part "HEADER/MALE/01NOBORDER"))
    )
    (comp (ref "P10")
      (value "HEADER/MALE/01NOBORDER")
      (footprint "eagle-import:HEADER_MALE_01_NOBORDER")
      (fields (field (name "SPICEPREFIX") "X"))
      (libsource (lib "eagle-import") (part "HEADER/MALE/01NOBORDER"))
    )
    (comp (ref "P11")
      (value "HEADER/MALE/01NOBORDER")
      (footprint "eagle-import:HEADER_MALE_01_NOBORDER")
      (fields (field (name "SPICEPREFIX") "X"))
      (libsource (lib "eagle-import") (part "HEADER/MALE/01NOBORDER"))
    )
    (comp (ref "P12")
      (value "HEADER/MALE/01NOBORDER")
      (footprint "eagle-import:HEADER_MALE_01_NOBORDER")
      (fields (field (name "SPICEPREFIX") "X"))
      (libsource (lib "eagle-import") (part "HEADER/MALE/01NOBORDER"))
    )
    (comp (ref "P13")
      (value "HEADER/MALE/01NOBORDER")
      (footprint "eagle-import:HEADER_MALE_01_NOBORDER")
      (fields (field (name "SPICEPREFIX") "X"))
      (libsource (lib "eagle-import") (part "HEADER/MALE/01NOBORDER"))
    )
    (comp (ref "P14")
      (value "HEADER/MALE/01NOBORDER")
      (footprint "eagle-import:HEADER_MALE_01_NOBORDER")
      (fields (field (name "SPICEPREFIX") "X"))
      (libsource (lib "eagle-import") (part "HEADER/MALE/01NOBORDER"))
    )
    (comp (ref "P15")
      (value "HEADER/MALE/01NOBORDER")
      (footprint "eagle-import:HEADER_MALE_01_NOBORDER")
      (fields (field (name "SPICEPREFIX") "X"))
      (libsource (lib "eagle-import") (part "HEADER/MALE/01NOBORDER"))
    )
    (comp (ref "P16")
      (value "HEADER/MALE/01NOBORDER")
      (footprint "eagle-import:HEADER_MALE_01_NOBORDER")
      (fields (field (name "SPICEPREFIX") "X"))
      (libsource (lib "eagle-import") (part "HEADER/MALE/01NOBORDER"))
    )
    (comp (ref "P17")
      (value "HEADER/MALE/01NOBORDER")
      (footprint "eagle-import:HEADER_MALE_01_NOBORDER")
      (fields (field (name "SPICEPREFIX") "X"))
      (libsource (lib "eagle-import") (part "HEADER/MALE/01NOBORDER"))
    )
    (comp (ref "P18")
      (value "HEADER/MALE/01NOBORDER")
      (footprint "eagle-import:HEADER_MALE_01_NOBORDER")
      (fields (field (name "SPICEPREFIX") "X"))
      (libsource (lib "eagle-import") (part "HEADER/MALE/01NOBORDER"))
    )
    (comp (ref "P19")
      (value "HEADER/MALE/01NOBORDER")
      (footprint "eagle-import:HEADER_MALE_01_NOBORDER")
      (fields (field (name "SPICEPREFIX") "X"))
      (libsource (lib "eagle-import") (part "HEADER/MALE/01NOBORDER"))
    )
    (comp (ref "P21")
      (value "HEADER/MALE/01NOBORDER")
      (footprint "eagle-import:HEADER_MALE_01_NOBORDER")
      (fields (field (name "SPICEPREFIX") "X"))
      (libsource (lib "eagle-import") (part "HEADER/MALE/01NOBORDER"))
    )
    (comp (ref "P22")
      (value "HEADER/MALE/01NOBORDER")
      (footprint "eagle-import:HEADER_MALE_01_NOBORDER")
      (fields (field (name "SPICEPREFIX") "X"))
      (libsource (lib "eagle-import") (part "HEADER/MALE/01NOBORDER"))
    )
    (comp (ref "P23")
      (value "HEADER/MALE/01NOBORDER")
      (footprint "eagle-import:HEADER_MALE_01_NOBORDER")
      (fields (field (name "SPICEPREFIX") "X"))
      (libsource (lib "eagle-import") (part "HEADER/MALE/01NOBORDER"))
    )
    (comp (ref "P24")
      (value "HEADER/MALE/01NOBORDER")
      (footprint "eagle-import:HEADER_MALE_01_NOBORDER")
      (fields (field (name "SPICEPREFIX") "X"))
      (libsource (lib "eagle-import") (part "HEADER/MALE/01NOBORDER"))
    )
    (comp (ref "P25")
      (value "HEADER/MALE/01NOBORDER")
      (footprint "eagle-import:HEADER_MALE_01_NOBORDER")
      (fields (field (name "SPICEPREFIX") "X"))
      (libsource (lib "eagle-import") (part "HEADER/MALE/01NOBORDER"))
    )
    (comp (ref "P26")
      (value "HEADER/MALE/01NOBORDER")
      (footprint "eagle-import:HEADER_MALE_01_NOBORDER")
      (fields (field (name "SPICEPREFIX") "X"))
      (libsource (lib "eagle-import") (part "HEADER/MALE/01NOBORDER"))
    )
    (comp (ref "P27")
      (value "HEADER/MALE/01NOBORDER")
      (footprint "eagle-import:HEADER_MALE_01_NOBORDER")
      (fields (field (name "SPICEPREFIX") "X"))
      (libsource (lib "eagle-import") (part "HEADER/MALE/01NOBORDER"))
    )
    (comp (ref "P28")
      (value "HEADER/MALE/01NOBORDER")
      (footprint "eagle-import:HEADER_MALE_01_NOBORDER")
      (fields (field (name "SPICEPREFIX") "X"))
      (libsource (lib "eagle-import") (part "HEADER/MALE/01NOBORDER"))
    )
    (comp (ref "P29")
      (value "HEADER/MALE/01NOBORDER")
      (footprint "eagle-import:HEADER_MALE_01_NOBORDER")
      (fields (field (name "SPICEPREFIX") "X"))
      (libsource (lib "eagle-import") (part "HEADER/MALE/01NOBORDER"))
    )
    (comp (ref "P30")
      (value "HEADER/MALE/01NOBORDER")
      (footprint "eagle-import:HEADER_MALE_01_NOBORDER")
      (fields (field (name "SPICEPREFIX") "X"))
      (libsource (lib "eagle-import") (part "HEADER/MALE/01NOBORDER"))
    )
    (comp (ref "P31")
      (value "HEADER/MALE/01NOBORDER")
      (footprint "eagle-import:HEADER_MALE_01_NOBORDER")
      (fields (field (name "SPICEPREFIX") "X"))
      (libsource (lib "eagle-import") (part "HEADER/MALE/01NOBORDER"))
    )
    (comp (ref "P32")
      (value "HEADER/MALE/01NOBORDER")
      (footprint "eagle-import:HEADER_MALE_01_NOBORDER")
      (fields (field (name "SPICEPREFIX") "X"))
      (libsource (lib "eagle-import") (part "HEADER/MALE/01NOBORDER"))
    )
    (comp (ref "P33")
      (value "HEADER/MALE/01NOBORDER")
      (footprint "eagle-import:HEADER_MALE_01_NOBORDER")
      (fields (field (name "SPICEPREFIX") "X"))
      (libsource (lib "eagle-import") (part "HEADER/MALE/01NOBORDER"))
    )
    (comp (ref "P34")
      (value "HEADER/MALE/01NOBORDER")
      (footprint "eagle-import:HEADER_MALE_01_NOBORDER")
      (fields (field (name "SPICEPREFIX") "X"))
      (libsource (lib "eagle-import") (part "HEADER/MALE/01NOBORDER"))
    )
    (comp (ref "P35")
      (value "HEADER/MALE/01NOBORDER")
      (footprint "eagle-import:HEADER_MALE_01_NOBORDER")
      (fields (field (name "SPICEPREFIX") "X"))
      (libsource (lib "eagle-import") (part "HEADER/MALE/01NOBORDER"))
    )
    (comp (ref "P36")
      (value "HEADER/MALE/01NOBORDER")
      (footprint "eagle-import:HEADER_MALE_01_NOBORDER")
      (fields (field (name "SPICEPREFIX") "X"))
      (libsource (lib "eagle-import") (part "HEADER/MALE/01NOBORDER"))
    )
    (comp (ref "P37")
      (value "HEADER/MALE/01NOBORDER")
      (footprint "eagle-import:HEADER_MALE_01_NOBORDER")
      (fields (field (name "SPICEPREFIX") "X"))
      (libsource (lib "eagle-import") (part "HEADER/MALE/01NOBORDER"))
    )
    (comp (ref "P38")
      (value "HEADER/MALE/01NOBORDER")
      (footprint "eagle-import:HEADER_MALE_01_NOBORDER")
      (fields (field (name "SPICEPREFIX") "X"))
      (libsource (lib "eagle-import") (part "HEADER/MALE/01NOBORDER"))
    )
    (comp (ref "P39")
      (value "HEADER/MALE/01NOBORDER")
      (footprint "eagle-import:HEADER_MALE_01_NOBORDER")
      (fields (field (name "SPICEPREFIX") "X"))
      (libsource (lib "eagle-import") (part "HEADER/MALE/01NOBORDER"))
    )
    (comp (ref "P40")
      (value "HEADER/MALE/01NOBORDER")
      (footprint "eagle-import:HEADER_MALE_01_NOBORDER")
      (fields (field (name "SPICEPREFIX") "X"))
      (libsource (lib "eagle-import") (part "HEADER/MALE/01NOBORDER"))
    )
    (comp (ref "P41")
      (value "HEADER/MALE/01NOBORDER")
      (footprint "eagle-import:HEADER_MALE_01_NOBORDER")
      (fields (field (name "SPICEPREFIX") "X"))
      (libsource (lib "eagle-import") (part "HEADER/MALE/01NOBORDER"))
    )
    (comp (ref "P42")
      (value "HEADER/MALE/01NOBORDER")
      (footprint "eagle-import:HEADER_MALE_01_NOBORDER")
      (fields (field (name "SPICEPREFIX") "X"))
      (libsource (lib "eagle-import") (part "HEADER/MALE/01NOBORDER"))
    )
    (comp (ref "P44")
      (value "HEADER/MALE/01NOBORDER")
      (footprint "eagle-import:HEADER_MALE_01_NOBORDER")
      (fields (field (name "SPICEPREFIX") "X"))
      (libsource (lib "eagle-import") (part "HEADER/MALE/01NOBORDER"))
    )
    (comp (ref "P45")
      (value "HEADER/MALE/01NOBORDER")
      (footprint "eagle-import:HEADER_MALE_01_NOBORDER")
      (fields (field (name "SPICEPREFIX") "X"))
      (libsource (lib "eagle-import") (part "HEADER/MALE/01NOBORDER"))
    )
    (comp (ref "P46")
      (value "HEADER/MALE/01NOBORDER")
      (footprint "eagle-import:HEADER_MALE_01_NOBORDER")
      (fields (field (name "SPICEPREFIX") "X"))
      (libsource (lib "eagle-import") (part "HEADER/MALE/01NOBORDER"))
    )
    (comp (ref "P47")
      (value "HEADER/MALE/01NOBORDER")
      (footprint "eagle-import:HEADER_MALE_01_NOBORDER")
      (fields (field (name "SPICEPREFIX") "X"))
      (libsource (lib "eagle-import") (part "HEADER/MALE/01NOBORDER"))
    )
    (comp (ref "P49")
      (value "HEADER/MALE/01NOBORDER")
      (footprint "eagle-import:HEADER_MALE_01_NOBORDER")
      (fields (field (name "SPICEPREFIX") "X"))
      (libsource (lib "eagle-import") (part "HEADER/MALE/01NOBORDER"))
    )
    (comp (ref "P50")
      (value "HEADER/MALE/01NOBORDER")
      (footprint "eagle-import:HEADER_MALE_01_NOBORDER")
      (fields (field (name "SPICEPREFIX") "X"))
      (libsource (lib "eagle-import") (part "HEADER/MALE/01NOBORDER"))
    )
    (comp (ref "PT1")
      (value "HEADER/MALE/01")
      (footprint "eagle-import:HEADER_MALE_01")
      (fields (field (name "SPICEPREFIX") "X"))
      (libsource (lib "eagle-import") (part "HEADER/MALE/01"))
    )
    (comp (ref "PT2")
      (value "HEADER/MALE/01")
      (footprint "eagle-import:HEADER_MALE_01")
      (fields (field (name "SPICEPREFIX") "X"))
      (libsource (lib "eagle-import") (part "HEADER/MALE/01"))
    )
    (comp (ref "PT3")
      (value "HEADER/MALE/01")
      (footprint "eagle-import:HEADER_MALE_01")
      (fields (field (name "SPICEPREFIX") "X"))
      (libsource (lib "eagle-import") (part "HEADER/MALE/01"))
    )
    (comp (ref "PT4")
      (value "HEADER/MALE/01")
      (footprint "eagle-import:HEADER_MALE_01")
      (fields (field (name "SPICEPREFIX") "X"))
      (libsource (lib "eagle-import") (part "HEADER/MALE/01"))
    )
    (comp (ref "PT5")
      (value "HEADER/MALE/01")
      (footprint "eagle-import:HEADER_MALE_01")
      (fields (field (name "SPICEPREFIX") "X"))
      (libsource (lib "eagle-import") (part "HEADER/MALE/01"))
    )
    (comp (ref "PT6")
      (value "HEADER/MALE/01")
      (footprint "eagle-import:HEADER_MALE_01")
      (fields (field (name "SPICEPREFIX") "X"))
      (libsource (lib "eagle-import") (part "HEADER/MALE/01"))
    )
    (comp (ref "PT7")
      (value "HEADER/MALE/01")
      (footprint "eagle-import:HEADER_MALE_01")
      (fields (field (name "SPICEPREFIX") "X"))
      (libsource (lib "eagle-import") (part "HEADER/MALE/01"))
    )
    (comp (ref "PT8")
      (value "HEADER/MALE/01")
      (footprint "eagle-import:HEADER_MALE_01")
      (fields (field (name "SPICEPREFIX") "X"))
      (libsource (lib "eagle-import") (part "HEADER/MALE/01"))
    )
    (comp (ref "Q1")
      (value "BF170")
      (footprint "eagle-import:SOT23")
      (libsource (lib "eagle-import") (part "BS170SOT23"))
    )
    (comp (ref "Q2")
      (value "BF170")
      (footprint "eagle-import:SOT23")
      (libsource (lib "eagle-import") (part "BS170SOT23"))
    )
    (comp (ref "Q3")
      (value "BF170")
      (footprint "eagle-import:SOT23")
      (libsource (lib "eagle-import") (part "BS170SOT23"))
    )
    (comp (ref "Q4")
      (value "BF170")
      (footprint "eagle-import:SOT23")
      (libsource (lib "eagle-import") (part "BS170SOT23"))
    )
    (comp (ref "Q5")
      (value "BF170")
      (footprint "eagle-import:SOT23")
      (libsource (lib "eagle-import") (part "BS170SOT23"))
    )
    (comp (ref "Q6")
      (value "BF170")
      (footprint "eagle-import:SOT23")
      (libsource (lib "eagle-import") (part "BS170SOT23"))
    )
    (comp (ref "Q7")
      (value "BF170")
      (footprint "eagle-import:SOT23")
      (libsource (lib "eagle-import") (part "BS170SOT23"))
    )
    (comp (ref "Q8")
      (value "BF170")
      (footprint "eagle-import:SOT23")
      (libsource (lib "eagle-import") (part "BS170SOT23"))
    )
    (comp (ref "Q9")
      (value "BF170")
      (footprint "eagle-import:SOT23")
      (libsource (lib "eagle-import") (part "BS170SOT23"))
    )
    (comp (ref "Q10")
      (value "BF170")
      (footprint "eagle-import:SOT23")
      (libsource (lib "eagle-import") (part "BS170SOT23"))
    )
    (comp (ref "Q11")
      (value "BF170")
      (footprint "eagle-import:SOT23")
      (libsource (lib "eagle-import") (part "BS170SOT23"))
    )
    (comp (ref "Q12")
      (value "BF170")
      (footprint "eagle-import:SOT23")
      (libsource (lib "eagle-import") (part "BS170SOT23"))
    )
    (comp (ref "Q13")
      (value "BF170")
      (footprint "eagle-import:SOT23")
      (libsource (lib "eagle-import") (part "BS170SOT23"))
    )
    (comp (ref "Q14")
      (value "BF170")
      (footprint "eagle-import:SOT23")
      (libsource (lib "eagle-import") (part "BS170SOT23"))
    )
    (comp (ref "Q15")
      (value "BF170")
      (footprint "eagle-import:SOT23")
      (libsource (lib "eagle-import") (part "BS170SOT23"))
    )
    (comp (ref "Q16")
      (value "BF170")
      (footprint "eagle-import:SOT23")
      (libsource (lib "eagle-import") (part "BS170SOT23"))
    )
    (comp (ref "R1")
      (value "120k")
      (footprint "eagle-import:R0603")
      (libsource (lib "eagle-import") (part "RESISTOR"))
    )
    (comp (ref "R2")
      (value "30k")
      (footprint "eagle-import:R0603")
      (libsource (lib "eagle-import") (part "RESISTOR"))
    )
    (comp (ref "R3")
      (value "1k")
      (footprint "eagle-import:R0603")
      (libsource (lib "eagle-import") (part "RESISTOR"))
    )
    (comp (ref "R4")
      (value "120k")
      (footprint "eagle-import:R0603")
      (libsource (lib "eagle-import") (part "RESISTOR"))
    )
    (comp (ref "R5")
      (value "30k")
      (footprint "eagle-import:R0603")
      (libsource (lib "eagle-import") (part "RESISTOR"))
    )
    (comp (ref "R6")
      (value "1k")
      (footprint "eagle-import:R0603")
      (libsource (lib "eagle-import") (part "RESISTOR"))
    )
    (comp (ref "R7")
      (value "2K")
      (footprint "eagle-import:R0603")
      (libsource (lib "eagle-import") (part "RESISTOR"))
    )
    (comp (ref "R8")
      (value "33k")
      (footprint "eagle-import:R0603")
      (libsource (lib "eagle-import") (part "RESISTOR"))
    )
    (comp (ref "R9")
      (value "120k")
      (footprint "eagle-import:R0603")
      (libsource (lib "eagle-import") (part "RESISTOR"))
    )
    (comp (ref "R10")
      (value "30k")
      (footprint "eagle-import:R0603")
      (libsource (lib "eagle-import") (part "RESISTOR"))
    )
    (comp (ref "R11")
      (value "100k")
      (footprint "eagle-import:R0603")
      (libsource (lib "eagle-import") (part "RESISTOR"))
    )
    (comp (ref "R12")
      (value "100k")
      (footprint "eagle-import:R0603")
      (libsource (lib "eagle-import") (part "RESISTOR"))
    )
    (comp (ref "R13")
      (value "100k")
      (footprint "eagle-import:R0603")
      (libsource (lib "eagle-import") (part "RESISTOR"))
    )
    (comp (ref "R14")
      (value "1k")
      (footprint "eagle-import:R0603")
      (libsource (lib "eagle-import") (part "RESISTOR"))
    )
    (comp (ref "R15")
      (value "33k")
      (footprint "eagle-import:R0603")
      (libsource (lib "eagle-import") (part "RESISTOR"))
    )
    (comp (ref "R16")
      (value "120k")
      (footprint "eagle-import:R0603")
      (libsource (lib "eagle-import") (part "RESISTOR"))
    )
    (comp (ref "R17")
      (value "30k")
      (footprint "eagle-import:R0603")
      (libsource (lib "eagle-import") (part "RESISTOR"))
    )
    (comp (ref "R18")
      (value "1k")
      (footprint "eagle-import:R0603")
      (libsource (lib "eagle-import") (part "RESISTOR"))
    )
    (comp (ref "R19")
      (value "120k")
      (footprint "eagle-import:R0603")
      (libsource (lib "eagle-import") (part "RESISTOR"))
    )
    (comp (ref "R20")
      (value "30k")
      (footprint "eagle-import:R0603")
      (libsource (lib "eagle-import") (part "RESISTOR"))
    )
    (comp (ref "R21")
      (value "33k")
      (footprint "eagle-import:R0603")
      (libsource (lib "eagle-import") (part "RESISTOR"))
    )
    (comp (ref "R22")
      (value "100k")
      (footprint "eagle-import:R0603")
      (libsource (lib "eagle-import") (part "RESISTOR"))
    )
    (comp (ref "R23")
      (value "100k")
      (footprint "eagle-import:R0603")
      (libsource (lib "eagle-import") (part "RESISTOR"))
    )
    (comp (ref "R24")
      (value "100k")
      (footprint "eagle-import:R0603")
      (libsource (lib "eagle-import") (part "RESISTOR"))
    )
    (comp (ref "R25")
      (value "33k")
      (footprint "eagle-import:R0603")
      (libsource (lib "eagle-import") (part "RESISTOR"))
    )
    (comp (ref "R26")
      (value "100k")
      (footprint "eagle-import:R0603")
      (libsource (lib "eagle-import") (part "RESISTOR"))
    )
    (comp (ref "R27")
      (value "100k")
      (footprint "eagle-import:R0603")
      (libsource (lib "eagle-import") (part "RESISTOR"))
    )
    (comp (ref "R28")
      (value "100k")
      (footprint "eagle-import:R0603")
      (libsource (lib "eagle-import") (part "RESISTOR"))
    )
    (comp (ref "R29")
      (value "100k")
      (footprint "eagle-import:R0603")
      (libsource (lib "eagle-import") (part "RESISTOR"))
    )
    (comp (ref "R30")
      (value "33k")
      (footprint "eagle-import:R0603")
      (libsource (lib "eagle-import") (part "RESISTOR"))
    )
    (comp (ref "R31")
      (value "100k")
      (footprint "eagle-import:R0603")
      (libsource (lib "eagle-import") (part "RESISTOR"))
    )
    (comp (ref "R32")
      (value "100k")
      (footprint "eagle-import:R0603")
      (libsource (lib "eagle-import") (part "RESISTOR"))
    )
    (comp (ref "R33")
      (value "100k")
      (footprint "eagle-import:R0603")
      (libsource (lib "eagle-import") (part "RESISTOR"))
    )
    (comp (ref "R34")
      (value "33k")
      (footprint "eagle-import:R0603")
      (libsource (lib "eagle-import") (part "RESISTOR"))
    )
    (comp (ref "R35")
      (value "100k")
      (footprint "eagle-import:R0603")
      (libsource (lib "eagle-import") (part "RESISTOR"))
    )
    (comp (ref "R36")
      (value "100k")
      (footprint "eagle-import:R0603")
      (libsource (lib "eagle-import") (part "RESISTOR"))
    )
    (comp (ref "R37")
      (value "100k")
      (footprint "eagle-import:R0603")
      (libsource (lib "eagle-import") (part "RESISTOR"))
    )
    (comp (ref "R38")
      (value "1k")
      (footprint "eagle-import:R0603")
      (libsource (lib "eagle-import") (part "RESISTOR"))
    )
    (comp (ref "R39")
      (value "120k")
      (footprint "eagle-import:R0603")
      (libsource (lib "eagle-import") (part "RESISTOR"))
    )
    (comp (ref "R40")
      (value "30k")
      (footprint "eagle-import:R0603")
      (libsource (lib "eagle-import") (part "RESISTOR"))
    )
    (comp (ref "R41")
      (value "1k")
      (footprint "eagle-import:R0603")
      (libsource (lib "eagle-import") (part "RESISTOR"))
    )
    (comp (ref "R42")
      (value "120k")
      (footprint "eagle-import:R0603")
      (libsource (lib "eagle-import") (part "RESISTOR"))
    )
    (comp (ref "R43")
      (value "30k")
      (footprint "eagle-import:R0603")
      (libsource (lib "eagle-import") (part "RESISTOR"))
    )
    (comp (ref "R44")
      (value "1k")
      (footprint "eagle-import:R0603")
      (libsource (lib "eagle-import") (part "RESISTOR"))
    )
    (comp (ref "R45")
      (value "120k")
      (footprint "eagle-import:R0603")
      (libsource (lib "eagle-import") (part "RESISTOR"))
    )
    (comp (ref "R46")
      (value "30k")
      (footprint "eagle-import:R0603")
      (libsource (lib "eagle-import") (part "RESISTOR"))
    )
    (comp (ref "R47")
      (value "1k")
      (footprint "eagle-import:R0603")
      (libsource (lib "eagle-import") (part "RESISTOR"))
    )
    (comp (ref "R48")
      (value "120k")
      (footprint "eagle-import:R0603")
      (libsource (lib "eagle-import") (part "RESISTOR"))
    )
    (comp (ref "R49")
      (value "120k")
      (footprint "eagle-import:R0603")
      (libsource (lib "eagle-import") (part "RESISTOR"))
    )
    (comp (ref "R50")
      (value "120k")
      (footprint "eagle-import:R0603")
      (libsource (lib "eagle-import") (part "RESISTOR"))
    )
    (comp (ref "R51")
      (value "120k")
      (footprint "eagle-import:R0603")
      (libsource (lib "eagle-import") (part "RESISTOR"))
    )
    (comp (ref "R52")
      (value "120k")
      (footprint "eagle-import:R0603")
      (libsource (lib "eagle-import") (part "RESISTOR"))
    )
    (comp (ref "R53")
      (value "120k")
      (footprint "eagle-import:R0603")
      (libsource (lib "eagle-import") (part "RESISTOR"))
    )
    (comp (ref "R54")
      (value "120k")
      (footprint "eagle-import:R0603")
      (libsource (lib "eagle-import") (part "RESISTOR"))
    )
    (comp (ref "R55")
      (value "120k")
      (footprint "eagle-import:R0603")
      (libsource (lib "eagle-import") (part "RESISTOR"))
    )
    (comp (ref "R56")
      (value "10k")
      (footprint "eagle-import:R0603")
      (libsource (lib "eagle-import") (part "RESISTOR"))
    )
    (comp (ref "R57")
      (value "10k")
      (footprint "eagle-import:R0603")
      (libsource (lib "eagle-import") (part "RESISTOR"))
    )
    (comp (ref "R58")
      (value "10k")
      (footprint "eagle-import:R0603")
      (libsource (lib "eagle-import") (part "RESISTOR"))
    )
    (comp (ref "R59")
      (value "10k")
      (footprint "eagle-import:R0603")
      (libsource (lib "eagle-import") (part "RESISTOR"))
    )
    (comp (ref "R60")
      (value "10k")
      (footprint "eagle-import:R0603")
      (libsource (lib "eagle-import") (part "RESISTOR"))
    )
    (comp (ref "R61")
      (value "10k")
      (footprint "eagle-import:R0603")
      (libsource (lib "eagle-import") (part "RESISTOR"))
    )
    (comp (ref "R62")
      (value "100k")
      (footprint "eagle-import:R0603")
      (libsource (lib "eagle-import") (part "RESISTOR"))
    )
    (comp (ref "R63")
      (value "100k")
      (footprint "eagle-import:R0603")
      (libsource (lib "eagle-import") (part "RESISTOR"))
    )
    (comp (ref "R64")
      (value "33k")
      (footprint "eagle-import:R0603")
      (libsource (lib "eagle-import") (part "RESISTOR"))
    )
    (comp (ref "R65")
      (value "100k")
      (footprint "eagle-import:R0603")
      (libsource (lib "eagle-import") (part "RESISTOR"))
    )
    (comp (ref "R66")
      (value "100k")
      (footprint "eagle-import:R0603")
      (libsource (lib "eagle-import") (part "RESISTOR"))
    )
    (comp (ref "R67")
      (value "100k")
      (footprint "eagle-import:R0603")
      (libsource (lib "eagle-import") (part "RESISTOR"))
    )
    (comp (ref "R68")
      (value "33k")
      (footprint "eagle-import:R0603")
      (libsource (lib "eagle-import") (part "RESISTOR"))
    )
    (comp (ref "R69")
      (value "100k")
      (footprint "eagle-import:R0603")
      (libsource (lib "eagle-import") (part "RESISTOR"))
    )
    (comp (ref "R70")
      (value "100k")
      (footprint "eagle-import:R0603")
      (libsource (lib "eagle-import") (part "RESISTOR"))
    )
    (comp (ref "R71")
      (value "100k")
      (footprint "eagle-import:R0603")
      (libsource (lib "eagle-import") (part "RESISTOR"))
    )
    (comp (ref "R72")
      (value "10k")
      (footprint "eagle-import:R0603")
      (libsource (lib "eagle-import") (part "RESISTOR"))
    )
    (comp (ref "R73")
      (value "10k")
      (footprint "eagle-import:R0603")
      (libsource (lib "eagle-import") (part "RESISTOR"))
    )
    (comp (ref "R74")
      (value "10k")
      (footprint "eagle-import:R0603")
      (libsource (lib "eagle-import") (part "RESISTOR"))
    )
    (comp (ref "R75")
      (value "10k")
      (footprint "eagle-import:R0603")
      (libsource (lib "eagle-import") (part "RESISTOR"))
    )
    (comp (ref "R76")
      (value "10k")
      (footprint "eagle-import:R0603")
      (libsource (lib "eagle-import") (part "RESISTOR"))
    )
    (comp (ref "R77")
      (value "10k")
      (footprint "eagle-import:R0603")
      (libsource (lib "eagle-import") (part "RESISTOR"))
    )
    (comp (ref "R78")
      (value "10k")
      (footprint "eagle-import:R0603")
      (libsource (lib "eagle-import") (part "RESISTOR"))
    )
    (comp (ref "R79")
      (value "10k")
      (footprint "eagle-import:R0603")
      (libsource (lib "eagle-import") (part "RESISTOR"))
    )
    (comp (ref "R80")
      (value "10k")
      (footprint "eagle-import:R0603")
      (libsource (lib "eagle-import") (part "RESISTOR"))
    )
    (comp (ref "R81")
      (value "10k")
      (footprint "eagle-import:R0603")
      (libsource (lib "eagle-import") (part "RESISTOR"))
    )
    (comp (ref "R82")
      (value "1k")
      (footprint "eagle-import:R0603")
      (libsource (lib "eagle-import") (part "RESISTOR"))
    )
    (comp (ref "R83")
      (value "120k")
      (footprint "eagle-import:R0603")
      (libsource (lib "eagle-import") (part "RESISTOR"))
    )
    (comp (ref "R84")
      (value "120k")
      (footprint "eagle-import:R0603")
      (libsource (lib "eagle-import") (part "RESISTOR"))
    )
    (comp (ref "R85")
      (value "120k")
      (footprint "eagle-import:R0603")
      (libsource (lib "eagle-import") (part "RESISTOR"))
    )
    (comp (ref "R86")
      (value "120k")
      (footprint "eagle-import:R0603")
      (libsource (lib "eagle-import") (part "RESISTOR"))
    )
    (comp (ref "R87")
      (value "120k")
      (footprint "eagle-import:R0603")
      (libsource (lib "eagle-import") (part "RESISTOR"))
    )
    (comp (ref "R88")
      (value "120k")
      (footprint "eagle-import:R0603")
      (libsource (lib "eagle-import") (part "RESISTOR"))
    )
    (comp (ref "R89")
      (value "120k")
      (footprint "eagle-import:R0603")
      (libsource (lib "eagle-import") (part "RESISTOR"))
    )
    (comp (ref "R90")
      (value "120k")
      (footprint "eagle-import:R0603")
      (libsource (lib "eagle-import") (part "RESISTOR"))
    )
    (comp (ref "R91")
      (value "0R")
      (footprint "eagle-import:R0603")
      (libsource (lib "eagle-import") (part "RESISTOR"))
    )
    (comp (ref "R92")
      (value "0R")
      (footprint "eagle-import:R0603")
      (libsource (lib "eagle-import") (part "RESISTOR"))
    )
    (comp (ref "R93")
      (value "0R")
      (footprint "eagle-import:R0603")
      (libsource (lib "eagle-import") (part "RESISTOR"))
    )
    (comp (ref "R94")
      (value "0R")
      (footprint "eagle-import:R0603")
      (libsource (lib "eagle-import") (part "RESISTOR"))
    )
    (comp (ref "R99")
      (value "10k")
      (footprint "eagle-import:R0603")
      (libsource (lib "eagle-import") (part "RESISTOR"))
    )
    (comp (ref "R100")
      (value "10k")
      (footprint "eagle-import:R0603")
      (libsource (lib "eagle-import") (part "RESISTOR"))
    )
    (comp (ref "R101")
      (value "10k")
      (footprint "eagle-import:R0603")
      (libsource (lib "eagle-import") (part "RESISTOR"))
    )
    (comp (ref "R102")
      (value "10k")
      (footprint "eagle-import:R0603")
      (libsource (lib "eagle-import") (part "RESISTOR"))
    )
    (comp (ref "R103")
      (value "10k")
      (footprint "eagle-import:R0603")
      (libsource (lib "eagle-import") (part "RESISTOR"))
    )
    (comp (ref "R104")
      (value "10k")
      (footprint "eagle-import:R0603")
      (libsource (lib "eagle-import") (part "RESISTOR"))
    )
    (comp (ref "R105")
      (value "10k")
      (footprint "eagle-import:R0603")
      (libsource (lib "eagle-import") (part "RESISTOR"))
    )
    (comp (ref "R106")
      (value "10k")
      (footprint "eagle-import:R0603")
      (libsource (lib "eagle-import") (part "RESISTOR"))
    )
    (comp (ref "R107")
      (value "10k")
      (footprint "eagle-import:R0603")
      (libsource (lib "eagle-import") (part "RESISTOR"))
    )
    (comp (ref "R108")
      (value "10k")
      (footprint "eagle-import:R0603")
      (libsource (lib "eagle-import") (part "RESISTOR"))
    )
    (comp (ref "R109")
      (value "10k")
      (footprint "eagle-import:R0603")
      (libsource (lib "eagle-import") (part "RESISTOR"))
    )
    (comp (ref "R110")
      (value "10k")
      (footprint "eagle-import:R0603")
      (libsource (lib "eagle-import") (part "RESISTOR"))
    )
    (comp (ref "R111")
      (value "10k")
      (footprint "eagle-import:R0603")
      (libsource (lib "eagle-import") (part "RESISTOR"))
    )
    (comp (ref "R112")
      (value "10k")
      (footprint "eagle-import:R0603")
      (libsource (lib "eagle-import") (part "RESISTOR"))
    )
    (comp (ref "R113")
      (value "10k")
      (footprint "eagle-import:R0603")
      (libsource (lib "eagle-import") (part "RESISTOR"))
    )
    (comp (ref "R114")
      (value "10k")
      (footprint "eagle-import:R0603")
      (libsource (lib "eagle-import") (part "RESISTOR"))
    )
    (comp (ref "R115")
      (value "2K")
      (footprint "eagle-import:R0603")
      (libsource (lib "eagle-import") (part "RESISTOR"))
    )
    (comp (ref "R116")
      (value "2K")
      (footprint "eagle-import:R0603")
      (libsource (lib "eagle-import") (part "RESISTOR"))
    )
  )
  (nets
    (net (code "1") (name "+12V") (class "Default")
      (node (ref "+V") (pin "1") (pinfunction "3_1") (pintype "passive"))
      (node (ref "+V1") (pin "1") (pinfunction "3_1") (pintype "passive"))
      (node (ref "+V2") (pin "1") (pinfunction "3_1") (pintype "passive"))
      (node (ref "+V3") (pin "1") (pinfunction "3_1") (pintype "passive"))
      (node (ref "+V4") (pin "1") (pinfunction "3_1") (pintype "passive"))
      (node (ref "+V5") (pin "1") (pinfunction "3_1") (pintype "passive"))
      (node (ref "C1") (pin "+") (pinfunction "+_+") (pintype "passive"))
      (node (ref "C23") (pin "2") (pinfunction "2_2") (pintype "passive"))
      (node (ref "C26") (pin "2") (pinfunction "2_2") (pintype "passive"))
      (node (ref "IC1") (pin "4") (pinfunction "V+_4") (pintype "power_in"))
      (node (ref "IC5") (pin "4") (pinfunction "V+_4") (pintype "power_in"))
      (node (ref "L1") (pin "1") (pinfunction "1_1") (pintype "passive"))
      (node (ref "L2") (pin "1") (pinfunction "1_1") (pintype "passive"))
    )
    (net (code "2") (name "-12V") (class "Default")
      (node (ref "-V") (pin "1") (pinfunction "3_1") (pintype "passive"))
      (node (ref "-V1") (pin "1") (pinfunction "3_1") (pintype "passive"))
      (node (ref "-V2") (pin "1") (pinfunction "3_1") (pintype "passive"))
      (node (ref "-V3") (pin "1") (pinfunction "3_1") (pintype "passive"))
      (node (ref "-V4") (pin "1") (pinfunction "3_1") (pintype "passive"))
      (node (ref "-V5") (pin "1") (pinfunction "3_1") (pintype "passive"))
      (node (ref "C2") (pin "-") (pinfunction "-_-") (pintype "passive"))
      (node (ref "C24") (pin "1") (pinfunction "1_1") (pintype "passive"))
      (node (ref "C25") (pin "1") (pinfunction "1_1") (pintype "passive"))
      (node (ref "IC1") (pin "11") (pinfunction "V-_11") (pintype "power_in"))
      (node (ref "IC5") (pin "11") (pinfunction "V-_11") (pintype "power_in"))
      (node (ref "R7") (pin "2") (pinfunction "2_2") (pintype "passive"))
    )
    (net (code "3") (name "/-5VREF") (class "Default")
      (node (ref "-5V") (pin "1") (pinfunction "3_1") (pintype "passive"))
      (node (ref "-5V1") (pin "1") (pinfunction "3_1") (pintype "passive"))
      (node (ref "-5V2") (pin "1") (pinfunction "3_1") (pintype "passive"))
      (node (ref "-5V3") (pin "1") (pinfunction "3_1") (pintype "passive"))
      (node (ref "C6") (pin "2") (pinfunction "2_2") (pintype "passive"))
      (node (ref "IC8") (pin "2") (pinfunction "A_2") (pintype "output"))
      (node (ref "R13") (pin "1") (pinfunction "1_1") (pintype "passive"))
      (node (ref "R24") (pin "1") (pinfunction "1_1") (pintype "passive"))
      (node (ref "R26") (pin "1") (pinfunction "1_1") (pintype "passive"))
      (node (ref "R29") (pin "1") (pinfunction "1_1") (pintype "passive"))
      (node (ref "R33") (pin "1") (pinfunction "1_1") (pintype "passive"))
      (node (ref "R37") (pin "1") (pinfunction "1_1") (pintype "passive"))
      (node (ref "R48") (pin "1") (pinfunction "1_1") (pintype "passive"))
      (node (ref "R49") (pin "1") (pinfunction "1_1") (pintype "passive"))
      (node (ref "R50") (pin "1") (pinfunction "1_1") (pintype "passive"))
      (node (ref "R51") (pin "1") (pinfunction "1_1") (pintype "passive"))
      (node (ref "R52") (pin "1") (pinfunction "1_1") (pintype "passive"))
      (node (ref "R53") (pin "1") (pinfunction "1_1") (pintype "passive"))
      (node (ref "R54") (pin "1") (pinfunction "1_1") (pintype "passive"))
      (node (ref "R55") (pin "1") (pinfunction "1_1") (pintype "passive"))
      (node (ref "R67") (pin "1") (pinfunction "1_1") (pintype "passive"))
      (node (ref "R7") (pin "1") (pinfunction "1_1") (pintype "passive"))
      (node (ref "R71") (pin "1") (pinfunction "1_1") (pintype "passive"))
    )
    (net (code "4") (name "/ADC0") (class "Default")
      (node (ref "C7") (pin "2") (pinfunction "2_2") (pintype "passive"))
      (node (ref "IC3") (pin "1") (pinfunction "OUT_1") (pintype "output"))
      (node (ref "IC6") (pin "14-A0/TX3/SPDIF_OUT") (pinfunction "14-A0/TX3/SPDIF_OUT_14-A0/TX3/SPDIF_OUT") (pintype "bidirectional"))
      (node (ref "R8") (pin "2") (pinfunction "2_2") (pintype "passive"))
    )
    (net (code "5") (name "/ADC1") (class "Default")
      (node (ref "C14") (pin "2") (pinfunction "2_2") (pintype "passive"))
      (node (ref "IC3") (pin "14") (pinfunction "OUT_14") (pintype "output"))
      (node (ref "IC6") (pin "15-A1/RX3/SPDIF_IN") (pinfunction "15-A1/RX3/SPDIF_IN_15-A1/RX3/SPDIF_IN") (pintype "bidirectional"))
      (node (ref "R68") (pin "2") (pinfunction "2_2") (pintype "passive"))
    )
    (net (code "6") (name "/ADC2") (class "Default")
      (node (ref "C10") (pin "2") (pinfunction "2_2") (pintype "passive"))
      (node (ref "IC3") (pin "7") (pinfunction "OUT_7") (pintype "output"))
      (node (ref "IC6") (pin "16-A2/RX4/SCL1") (pinfunction "16-A2/RX4/SCL1_16-A2/RX4/SCL1") (pintype "bidirectional"))
      (node (ref "R15") (pin "2") (pinfunction "2_2") (pintype "passive"))
    )
    (net (code "7") (name "/ADC3") (class "Default")
      (node (ref "C11") (pin "2") (pinfunction "2_2") (pintype "passive"))
      (node (ref "IC3") (pin "8") (pinfunction "OUT_8") (pintype "output"))
      (node (ref "IC6") (pin "17-A3/TX4/SDA1") (pinfunction "17-A3/TX4/SDA1_17-A3/TX4/SDA1") (pintype "bidirectional"))
      (node (ref "R64") (pin "2") (pinfunction "2_2") (pintype "passive"))
    )
    (net (code "8") (name "/ADC4") (class "Default")
      (node (ref "C16") (pin "2") (pinfunction "2_2") (pintype "passive"))
      (node (ref "IC4") (pin "1") (pinfunction "OUT_1") (pintype "output"))
      (node (ref "IC6") (pin "20-A6/TX5/LRCLK1") (pinfunction "20-A6/TX5/LRCLK1_20-A6/TX5/LRCLK1") (pintype "bidirectional"))
      (node (ref "R21") (pin "2") (pinfunction "2_2") (pintype "passive"))
    )
    (net (code "9") (name "/ADC5") (class "Default")
      (node (ref "C21") (pin "2") (pinfunction "2_2") (pintype "passive"))
      (node (ref "IC4") (pin "14") (pinfunction "OUT_14") (pintype "output"))
      (node (ref "IC6") (pin "21-A7/RX5/BCLK1") (pinfunction "21-A7/RX5/BCLK1_21-A7/RX5/BCLK1") (pintype "bidirectional"))
      (node (ref "R34") (pin "2") (pinfunction "2_2") (pintype "passive"))
    )
    (net (code "10") (name "/ADC6") (class "Default")
      (node (ref "C17") (pin "2") (pinfunction "2_2") (pintype "passive"))
      (node (ref "IC4") (pin "7") (pinfunction "OUT_7") (pintype "output"))
      (node (ref "IC6") (pin "22-A8/CTX1") (pinfunction "22-A8/CTX1_22-A8/CTX1") (pintype "bidirectional"))
      (node (ref "R25") (pin "2") (pinfunction "2_2") (pintype "passive"))
    )
    (net (code "11") (name "/ADC7") (class "Default")
      (node (ref "C20") (pin "2") (pinfunction "2_2") (pintype "passive"))
      (node (ref "IC4") (pin "8") (pinfunction "OUT_8") (pintype "output"))
      (node (ref "IC6") (pin "23-A9/CRX1/MCLK1") (pinfunction "23-A9/CRX1/MCLK1_23-A9/CRX1/MCLK1") (pintype "bidirectional"))
      (node (ref "R30") (pin "2") (pinfunction "2_2") (pintype "passive"))
    )
    (net (code "12") (name "/ADC8") (class "Default")
      (node (ref "24_4.0-A10") (pin "1") (pinfunction "3_1") (pintype "passive"))
      (node (ref "24_LC-A10") (pin "1") (pinfunction "3_1") (pintype "passive"))
      (node (ref "IC12") (pin "3") (pinfunction "Z_3") (pintype "bidirectional"))
      (node (ref "IC6") (pin "24-A10/TX6/SCL2") (pinfunction "24-A10/TX6/SCL2_24-A10/TX6/SCL2") (pintype "bidirectional"))
      (node (ref "R91") (pin "2") (pinfunction "2_2") (pintype "passive"))
    )
    (net (code "13") (name "/ADC9") (class "Default")
      (node (ref "25_4.0-A11") (pin "1") (pinfunction "3_1") (pintype "passive"))
      (node (ref "25_LC-A11") (pin "1") (pinfunction "3_1") (pintype "passive"))
      (node (ref "IC12") (pin "9") (pinfunction "S2_9") (pintype "input"))
      (node (ref "IC6") (pin "25-A11/RX6/SDA2") (pinfunction "25-A11/RX6/SDA2_25-A11/RX6/SDA2") (pintype "bidirectional"))
      (node (ref "R92") (pin "2") (pinfunction "2_2") (pintype "passive"))
    )
    (net (code "14") (name "/ADC10") (class "Default")
      (node (ref "26_4.0-A12") (pin "1") (pinfunction "3_1") (pintype "passive"))
      (node (ref "26_LC-A12") (pin "1") (pinfunction "3_1") (pintype "passive"))
      (node (ref "IC12") (pin "10") (pinfunction "S1_10") (pintype "input"))
      (node (ref "IC6") (pin "26-A12/MOSI1") (pinfunction "26-A12/MOSI1_26-A12/MOSI1") (pintype "bidirectional"))
      (node (ref "R93") (pin "2") (pinfunction "2_2") (pintype "passive"))
    )
    (net (code "15") (name "/ADC11") (class "Default")
      (node (ref "27_4.0-A13") (pin "1") (pinfunction "3_1") (pintype "passive"))
      (node (ref "IC12") (pin "11") (pinfunction "S0_11") (pintype "input"))
      (node (ref "IC6") (pin "27-A13/SCK1") (pinfunction "27-A13/SCK1_27-A13/SCK1") (pintype "bidirectional"))
      (node (ref "R94") (pin "2") (pinfunction "2_2") (pintype "passive"))
    )
    (net (code "16") (name "/DAC1") (class "Default")
      (node (ref "DAC1") (pin "1") (pinfunction "3_1") (pintype "passive"))
      (node (ref "IC11") (pin "7") (pinfunction "VOUTC_7") (pintype "tri_state"))
      (node (ref "R46") (pin "1") (pinfunction "1_1") (pintype "passive"))
    )
    (net (code "17") (name "/DAC2") (class "Default")
      (node (ref "DAC2") (pin "1") (pinfunction "3_1") (pintype "passive"))
      (node (ref "IC11") (pin "2") (pinfunction "VOUTB_2") (pintype "tri_state"))
      (node (ref "R20") (pin "1") (pinfunction "1_1") (pintype "passive"))
    )
    (net (code "18") (name "/DAC3") (class "Default")
      (node (ref "DAC4") (pin "1") (pinfunction "3_1") (pintype "passive"))
      (node (ref "IC11") (pin "8") (pinfunction "VOUTD_8") (pintype "tri_state"))
      (node (ref "R43") (pin "1") (pinfunction "1_1") (pintype "passive"))
    )
    (net (code "19") (name "/DAC4") (class "Default")
      (node (ref "DAC3") (pin "1") (pinfunction "3_1") (pintype "passive"))
      (node (ref "IC11") (pin "1") (pinfunction "VOUTA_1") (pintype "tri_state"))
      (node (ref "R40") (pin "1") (pinfunction "1_1") (pintype "passive"))
    )
    (net (code "20") (name "/DAC5") (class "Default")
      (node (ref "IC10") (pin "1") (pinfunction "VOUTA_1") (pintype "tri_state"))
      (node (ref "R17") (pin "1") (pinfunction "1_1") (pintype "passive"))
    )
    (net (code "21") (name "/DAC6") (class "Default")
      (node (ref "IC10") (pin "8") (pinfunction "VOUTD_8") (pintype "tri_state"))
      (node (ref "R2") (pin "1") (pinfunction "1_1") (pintype "passive"))
    )
    (net (code "22") (name "/DAC7") (class "Default")
      (node (ref "IC10") (pin "2") (pinfunction "VOUTB_2") (pintype "tri_state"))
      (node (ref "R10") (pin "1") (pinfunction "1_1") (pintype "passive"))
    )
    (net (code "23") (name "/DAC8") (class "Default")
      (node (ref "IC10") (pin "7") (pinfunction "VOUTC_7") (pintype "tri_state"))
      (node (ref "R5") (pin "1") (pinfunction "1_1") (pintype "passive"))
    )
    (net (code "24") (name "/GPA0") (class "Default")
      (node (ref "IC2") (pin "21") (pinfunction "GPA0_21") (pintype "bidirectional"))
      (node (ref "Q1") (pin "2") (pinfunction "S_2") (pintype "passive"))
      (node (ref "R56") (pin "1") (pinfunction "1_1") (pintype "passive"))
    )
    (net (code "25") (name "/GPA1") (class "Default")
      (node (ref "IC2") (pin "22") (pinfunction "GPA1_22") (pintype "bidirectional"))
      (node (ref "Q2") (pin "2") (pinfunction "S_2") (pintype "passive"))
      (node (ref "R57") (pin "1") (pinfunction "1_1") (pintype "passive"))
    )
    (net (code "26") (name "/GPA2") (class "Default")
      (node (ref "IC2") (pin "23") (pinfunction "GPA2_23") (pintype "bidirectional"))
      (node (ref "Q3") (pin "2") (pinfunction "S_2") (pintype "passive"))
      (node (ref "R59") (pin "1") (pinfunction "1_1") (pintype "passive"))
    )
    (net (code "27") (name "/GPA3") (class "Default")
      (node (ref "IC2") (pin "24") (pinfunction "GPA3_24") (pintype "bidirectional"))
      (node (ref "Q4") (pin "2") (pinfunction "S_2") (pintype "passive"))
      (node (ref "R61") (pin "1") (pinfunction "1_1") (pintype "passive"))
    )
    (net (code "28") (name "/GPA4") (class "Default")
      (node (ref "IC2") (pin "25") (pinfunction "GPA4_25") (pintype "bidirectional"))
      (node (ref "Q5") (pin "2") (pinfunction "S_2") (pintype "passive"))
      (node (ref "R73") (pin "1") (pinfunction "1_1") (pintype "passive"))
    )
    (net (code "29") (name "/GPA5") (class "Default")
      (node (ref "IC2") (pin "26") (pinfunction "GPA5_26") (pintype "bidirectional"))
      (node (ref "Q6") (pin "2") (pinfunction "S_2") (pintype "passive"))
      (node (ref "R75") (pin "1") (pinfunction "1_1") (pintype "passive"))
    )
    (net (code "30") (name "/GPA6") (class "Default")
      (node (ref "IC2") (pin "27") (pinfunction "GPA6_27") (pintype "bidirectional"))
      (node (ref "Q7") (pin "2") (pinfunction "S_2") (pintype "passive"))
      (node (ref "R77") (pin "1") (pinfunction "1_1") (pintype "passive"))
    )
    (net (code "31") (name "/GPA7") (class "Default")
      (node (ref "IC2") (pin "28") (pinfunction "GPA7_28") (pintype "bidirectional"))
      (node (ref "Q8") (pin "2") (pinfunction "S_2") (pintype "passive"))
      (node (ref "R79") (pin "1") (pinfunction "1_1") (pintype "passive"))
    )
    (net (code "32") (name "/GPB0") (class "Default")
      (node (ref "IC2") (pin "1") (pinfunction "GPB0_1") (pintype "bidirectional"))
      (node (ref "Q9") (pin "2") (pinfunction "S_2") (pintype "passive"))
      (node (ref "R81") (pin "1") (pinfunction "1_1") (pintype "passive"))
    )
    (net (code "33") (name "/GPB1") (class "Default")
      (node (ref "IC2") (pin "2") (pinfunction "GPB1_2") (pintype "bidirectional"))
      (node (ref "Q10") (pin "2") (pinfunction "S_2") (pintype "passive"))
      (node (ref "R101") (pin "1") (pinfunction "1_1") (pintype "passive"))
    )
    (net (code "34") (name "/GPB2") (class "Default")
      (node (ref "IC2") (pin "3") (pinfunction "GPB2_3") (pintype "bidirectional"))
      (node (ref "Q11") (pin "2") (pinfunction "S_2") (pintype "passive"))
      (node (ref "R103") (pin "1") (pinfunction "1_1") (pintype "passive"))
    )
    (net (code "35") (name "/GPB3") (class "Default")
      (node (ref "IC2") (pin "4") (pinfunction "GPB3_4") (pintype "bidirectional"))
      (node (ref "Q12") (pin "2") (pinfunction "S_2") (pintype "passive"))
      (node (ref "R105") (pin "1") (pinfunction "1_1") (pintype "passive"))
    )
    (net (code "36") (name "/GPB4") (class "Default")
      (node (ref "IC2") (pin "5") (pinfunction "GPB4_5") (pintype "bidirectional"))
      (node (ref "Q13") (pin "2") (pinfunction "S_2") (pintype "passive"))
      (node (ref "R107") (pin "1") (pinfunction "1_1") (pintype "passive"))
    )
    (net (code "37") (name "/GPB5") (class "Default")
      (node (ref "IC2") (pin "6") (pinfunction "GPB5_6") (pintype "bidirectional"))
      (node (ref "Q14") (pin "2") (pinfunction "S_2") (pintype "passive"))
      (node (ref "R109") (pin "1") (pinfunction "1_1") (pintype "passive"))
    )
    (net (code "38") (name "/GPB6") (class "Default")
      (node (ref "IC2") (pin "7") (pinfunction "GPB6_7") (pintype "bidirectional"))
      (node (ref "Q15") (pin "2") (pinfunction "S_2") (pintype "passive"))
      (node (ref "R111") (pin "1") (pinfunction "1_1") (pintype "passive"))
    )
    (net (code "39") (name "/GPB7") (class "Default")
      (node (ref "IC2") (pin "8") (pinfunction "GPB7_8") (pintype "bidirectional"))
      (node (ref "Q16") (pin "2") (pinfunction "S_2") (pintype "passive"))
      (node (ref "R113") (pin "1") (pinfunction "1_1") (pintype "passive"))
    )
    (net (code "40") (name "/INTA") (class "Default")
      (node (ref "6_INTA") (pin "1") (pinfunction "3_1") (pintype "passive"))
      (node (ref "IC2") (pin "20") (pinfunction "INTA_20") (pintype "output"))
      (node (ref "IC6") (pin "6-OUT1D") (pinfunction "6-OUT1D_6-OUT1D") (pintype "bidirectional"))
    )
    (net (code "41") (name "/INTB") (class "Default")
      (node (ref "7_INTB") (pin "1") (pinfunction "3_1") (pintype "passive"))
      (node (ref "IC2") (pin "19") (pinfunction "INTB_19") (pintype "output"))
      (node (ref "IC6") (pin "7-RX2/OUT1A") (pinfunction "7-RX2/OUT1A_7-RX2/OUT1A") (pintype "bidirectional"))
    )
    (net (code "42") (name "/OFFSET") (class "Default")
      (node (ref "OFFSET") (pin "1") (pinfunction "3_1") (pintype "passive"))
      (node (ref "R83") (pin "1") (pinfunction "1_1") (pintype "passive"))
      (node (ref "R84") (pin "1") (pinfunction "1_1") (pintype "passive"))
      (node (ref "R85") (pin "1") (pinfunction "1_1") (pintype "passive"))
      (node (ref "R86") (pin "1") (pinfunction "1_1") (pintype "passive"))
      (node (ref "R87") (pin "1") (pinfunction "1_1") (pintype "passive"))
      (node (ref "R88") (pin "1") (pinfunction "1_1") (pintype "passive"))
      (node (ref "R89") (pin "1") (pinfunction "1_1") (pintype "passive"))
      (node (ref "R90") (pin "1") (pinfunction "1_1") (pintype "passive"))
    )
    (net (code "43") (name "/SPI_CS_DAC1") (class "Default")
      (node (ref "9_DAC_CS") (pin "1") (pinfunction "3_1") (pintype "passive"))
      (node (ref "IC11") (pin "9") (pinfunction "~{SYNC}_9") (pintype "input"))
      (node (ref "IC6") (pin "9-OUT1C") (pinfunction "9-OUT1C_9-OUT1C") (pintype "bidirectional"))
    )
    (net (code "44") (name "/SPI_CS_DAC2") (class "Default")
      (node (ref "8_DAC_CS") (pin "1") (pinfunction "3_1") (pintype "passive"))
      (node (ref "IC10") (pin "9") (pinfunction "~{SYNC}_9") (pintype "input"))
      (node (ref "IC6") (pin "8-TX2/IN1") (pinfunction "8-TX2/IN1_8-TX2/IN1") (pintype "bidirectional"))
    )
    (net (code "45") (name "/SPI_IO_CS") (class "Default")
      (node (ref "10_IO_CS") (pin "1") (pinfunction "3_1") (pintype "passive"))
      (node (ref "IC2") (pin "11") (pinfunction "~{CS}_11") (pintype "input"))
      (node (ref "IC6") (pin "10-CS\\MQSR") (pinfunction "10-CS/MQSR_10-CS\\MQSR") (pintype "bidirectional"))
    )
    (net (code "46") (name "/SPI_MISO") (class "Default")
      (node (ref "12_MISO") (pin "1") (pinfunction "3_1") (pintype "passive"))
      (node (ref "IC2") (pin "14") (pinfunction "SO_14") (pintype "output"))
      (node (ref "IC6") (pin "12-MISO/MQSL") (pinfunction "12-MISO/MQSL_12-MISO/MQSL") (pintype "bidirectional"))
    )
    (net (code "47") (name "/SPI_MOSI") (class "Default")
      (node (ref "11_MOSI") (pin "1") (pinfunction "3_1") (pintype "passive"))
      (node (ref "IC10") (pin "11") (pinfunction "DIN_11") (pintype "input"))
      (node (ref "IC11") (pin "11") (pinfunction "DIN_11") (pintype "input"))
      (node (ref "IC2") (pin "13") (pinfunction "SI_13") (pintype "input"))
      (node (ref "IC6") (pin "11-MOSI/CTX1") (pinfunction "11-MOSI/CTX1_11-MOSI/CTX1") (pintype "bidirectional"))
    )
    (net (code "48") (name "/SPI_SCK") (class "Default")
      (node (ref "13_SCK") (pin "1") (pinfunction "3_1") (pintype "passive"))
      (node (ref "IC10") (pin "10") (pinfunction "SCLK_10") (pintype "input"))
      (node (ref "IC11") (pin "10") (pinfunction "SCLK_10") (pintype "input"))
      (node (ref "IC2") (pin "12") (pinfunction "SCK_12") (pintype "input"))
      (node (ref "IC6") (pin "13-SCK/LED") (pinfunction "13-SCK/LED_13-SCK/LED") (pintype "bidirectional"))
    )
    (net (code "49") (name "3.3V") (class "Default")
      (node (ref "3.3V") (pin "1") (pinfunction "3_1") (pintype "passive"))
      (node (ref "3.3V1") (pin "1") (pinfunction "3_1") (pintype "passive"))
      (node (ref "3.3V2") (pin "1") (pinfunction "3_1") (pintype "passive"))
      (node (ref "3.3V3") (pin "1") (pinfunction "3_1") (pintype "passive"))
      (node (ref "IC10") (pin "12") (pinfunction "IOVDD_12") (pintype "power_in"))
      (node (ref "IC11") (pin "12") (pinfunction "IOVDD_12") (pintype "power_in"))
      (node (ref "IC2") (pin "9") (pinfunction "VDD_9") (pintype "power_in"))
      (node (ref "IC6") (pin "3V3-3") (pinfunction "3V3-3_3V3-3") (pintype "bidirectional"))
      (node (ref "Q1") (pin "1") (pinfunction "G_1") (pintype "passive"))
      (node (ref "Q10") (pin "1") (pinfunction "G_1") (pintype "passive"))
      (node (ref "Q11") (pin "1") (pinfunction "G_1") (pintype "passive"))
      (node (ref "Q12") (pin "1") (pinfunction "G_1") (pintype "passive"))
      (node (ref "Q13") (pin "1") (pinfunction "G_1") (pintype "passive"))
      (node (ref "Q14") (pin "1") (pinfunction "G_1") (pintype "passive"))
      (node (ref "Q15") (pin "1") (pinfunction "G_1") (pintype "passive"))
      (node (ref "Q16") (pin "1") (pinfunction "G_1") (pintype "passive"))
      (node (ref "Q2") (pin "1") (pinfunction "G_1") (pintype "passive"))
      (node (ref "Q3") (pin "1") (pinfunction "G_1") (pintype "passive"))
      (node (ref "Q4") (pin "1") (pinfunction "G_1") (pintype "passive"))
      (node (ref "Q5") (pin "1") (pinfunction "G_1") (pintype "passive"))
      (node (ref "Q6") (pin "1") (pinfunction "G_1") (pintype "passive"))
      (node (ref "Q7") (pin "1") (pinfunction "G_1") (pintype "passive"))
      (node (ref "Q8") (pin "1") (pinfunction "G_1") (pintype "passive"))
      (node (ref "Q9") (pin "1") (pinfunction "G_1") (pintype "passive"))
      (node (ref "R101") (pin "2") (pinfunction "2_2") (pintype "passive"))
      (node (ref "R103") (pin "2") (pinfunction "2_2") (pintype "passive"))
      (node (ref "R105") (pin "2") (pinfunction "2_2") (pintype "passive"))
      (node (ref "R107") (pin "2") (pinfunction "2_2") (pintype "passive"))
      (node (ref "R109") (pin "2") (pinfunction "2_2") (pintype "passive"))
      (node (ref "R111") (pin "2") (pinfunction "2_2") (pintype "passive"))
      (node (ref "R113") (pin "2") (pinfunction "2_2") (pintype "passive"))
      (node (ref "R115") (pin "2") (pinfunction "2_2") (pintype "passive"))
      (node (ref "R116") (pin "2") (pinfunction "2_2") (pintype "passive"))
      (node (ref "R56") (pin "2") (pinfunction "2_2") (pintype "passive"))
      (node (ref "R57") (pin "2") (pinfunction "2_2") (pintype "passive"))
      (node (ref "R59") (pin "2") (pinfunction "2_2") (pintype "passive"))
      (node (ref "R61") (pin "2") (pinfunction "2_2") (pintype "passive"))
      (node (ref "R73") (pin "2") (pinfunction "2_2") (pintype "passive"))
      (node (ref "R75") (pin "2") (pinfunction "2_2") (pintype "passive"))
      (node (ref "R77") (pin "2") (pinfunction "2_2") (pintype "passive"))
      (node (ref "R79") (pin "2") (pinfunction "2_2") (pintype "passive"))
      (node (ref "R81") (pin "2") (pinfunction "2_2") (pintype "passive"))
      (node (ref "R82") (pin "1") (pinfunction "1_1") (pintype "passive"))
    )
    (net (code "50") (name "3.3V_A") (class "Default")
      (node (ref "3.3VA") (pin "1") (pinfunction "3_1") (pintype "passive"))
      (node (ref "3.3VA1") (pin "1") (pinfunction "3_1") (pintype "passive"))
      (node (ref "3.3VA2") (pin "1") (pinfunction "3_1") (pintype "passive"))
      (node (ref "3.3VA3") (pin "1") (pinfunction "3_1") (pintype "passive"))
      (node (ref "C15") (pin "2") (pinfunction "2_2") (pintype "passive"))
      (node (ref "C18") (pin "2") (pinfunction "2_2") (pintype "passive"))
      (node (ref "C30") (pin "+") (pinfunction "+_+") (pintype "passive"))
      (node (ref "C32") (pin "2") (pinfunction "2_2") (pintype "passive"))
      (node (ref "IC10") (pin "4") (pinfunction "AVDD_4") (pintype "power_in"))
      (node (ref "IC11") (pin "4") (pinfunction "AVDD_4") (pintype "power_in"))
      (node (ref "IC12") (pin "16") (pinfunction "VCC_16") (pintype "power_in"))
      (node (ref "IC3") (pin "4") (pinfunction "V+_4") (pintype "power_in"))
      (node (ref "IC4") (pin "4") (pinfunction "V+_4") (pintype "power_in"))
      (node (ref "IC9") (pin "1") (pinfunction "VOUT_1") (pintype "power_in"))
    )
    (net (code "51") (name "5V") (class "Default")
      (node (ref "5V") (pin "1") (pinfunction "3_1") (pintype "passive"))
      (node (ref "5V1") (pin "1") (pinfunction "3_1") (pintype "passive"))
      (node (ref "5V2") (pin "1") (pinfunction "3_1") (pintype "passive"))
      (node (ref "5V3") (pin "1") (pinfunction "3_1") (pintype "passive"))
      (node (ref "C27") (pin "2") (pinfunction "2_2") (pintype "passive"))
      (node (ref "C3") (pin "+") (pinfunction "+_+") (pintype "passive"))
      (node (ref "IC6") (pin "VIN") (pinfunction "VIN_VIN") (pintype "bidirectional"))
      (node (ref "IC7") (pin "3") (pinfunction "VO_3") (pintype "passive"))
      (node (ref "R100") (pin "2") (pinfunction "2_2") (pintype "passive"))
      (node (ref "R102") (pin "2") (pinfunction "2_2") (pintype "passive"))
      (node (ref "R104") (pin "2") (pinfunction "2_2") (pintype "passive"))
      (node (ref "R106") (pin "2") (pinfunction "2_2") (pintype "passive"))
      (node (ref "R108") (pin "2") (pinfunction "2_2") (pintype "passive"))
      (node (ref "R110") (pin "2") (pinfunction "2_2") (pintype "passive"))
      (node (ref "R112") (pin "2") (pinfunction "2_2") (pintype "passive"))
      (node (ref "R114") (pin "2") (pinfunction "2_2") (pintype "passive"))
      (node (ref "R58") (pin "2") (pinfunction "2_2") (pintype "passive"))
      (node (ref "R60") (pin "2") (pinfunction "2_2") (pintype "passive"))
      (node (ref "R72") (pin "2") (pinfunction "2_2") (pintype "passive"))
      (node (ref "R74") (pin "2") (pinfunction "2_2") (pintype "passive"))
      (node (ref "R76") (pin "2") (pinfunction "2_2") (pintype "passive"))
      (node (ref "R78") (pin "2") (pinfunction "2_2") (pintype "passive"))
      (node (ref "R80") (pin "2") (pinfunction "2_2") (pintype "passive"))
      (node (ref "R99") (pin "2") (pinfunction "2_2") (pintype "passive"))
    )
    (net (code "52") (name "GND") (class "Default")
      (node (ref "C1") (pin "-") (pinfunction "-_-") (pintype "passive"))
      (node (ref "C15") (pin "1") (pinfunction "1_1") (pintype "passive"))
      (node (ref "C18") (pin "1") (pinfunction "1_1") (pintype "passive"))
      (node (ref "C2") (pin "+") (pinfunction "+_+") (pintype "passive"))
      (node (ref "C23") (pin "1") (pinfunction "1_1") (pintype "passive"))
      (node (ref "C24") (pin "2") (pinfunction "2_2") (pintype "passive"))
      (node (ref "C25") (pin "2") (pinfunction "2_2") (pintype "passive"))
      (node (ref "C26") (pin "1") (pinfunction "1_1") (pintype "passive"))
      (node (ref "C27") (pin "1") (pinfunction "1_1") (pintype "passive"))
      (node (ref "C28") (pin "1") (pinfunction "1_1") (pintype "passive"))
      (node (ref "C29") (pin "1") (pinfunction "1_1") (pintype "passive"))
      (node (ref "C3") (pin "-") (pinfunction "-_-") (pintype "passive"))
      (node (ref "C30") (pin "-") (pinfunction "-_-") (pintype "passive"))
      (node (ref "C32") (pin "1") (pinfunction "1_1") (pintype "passive"))
      (node (ref "C33") (pin "2") (pinfunction "2_2") (pintype "passive"))
      (node (ref "C34") (pin "2") (pinfunction "2_2") (pintype "passive"))
      (node (ref "C6") (pin "1") (pinfunction "1_1") (pintype "passive"))
      (node (ref "GND") (pin "1") (pinfunction "3_1") (pintype "passive"))
      (node (ref "GND1") (pin "1") (pinfunction "3_1") (pintype "passive"))
      (node (ref "GND2") (pin "1") (pinfunction "3_1") (pintype "passive"))
      (node (ref "GND3") (pin "1") (pinfunction "3_1") (pintype "passive"))
      (node (ref "GND4") (pin "1") (pinfunction "3_1") (pintype "passive"))
      (node (ref "GND5") (pin "1") (pinfunction "3_1") (pintype "passive"))
      (node (ref "GND6") (pin "1") (pinfunction "3_1") (pintype "passive"))
      (node (ref "GND7") (pin "1") (pinfunction "3_1") (pintype "passive"))
      (node (ref "GND8") (pin "1") (pinfunction "3_1") (pintype "passive"))
      (node (ref "GND9") (pin "1") (pinfunction "3_1") (pintype "passive"))
      (node (ref "IC1") (pin "10") (pinfunction "+IN_10") (pintype "input"))
      (node (ref "IC1") (pin "12") (pinfunction "+IN_12") (pintype "input"))
      (node (ref "IC1") (pin "3") (pinfunction "+IN_3") (pintype "input"))
      (node (ref "IC1") (pin "5") (pinfunction "+IN_5") (pintype "input"))
      (node (ref "IC10") (pin "13") (pinfunction "A0_13") (pintype "input"))
      (node (ref "IC10") (pin "14") (pinfunction "A1_14") (pintype "input"))
      (node (ref "IC10") (pin "15") (pinfunction "~{ENABLE}_15") (pintype "input"))
      (node (ref "IC10") (pin "16") (pinfunction "LDAC_16") (pintype "input"))
      (node (ref "IC10") (pin "5") (pinfunction "VREFL_5") (pintype "input"))
      (node (ref "IC10") (pin "6") (pinfunction "GND_6") (pintype "power_in"))
      (node (ref "IC11") (pin "13") (pinfunction "A0_13") (pintype "input"))
      (node (ref "IC11") (pin "14") (pinfunction "A1_14") (pintype "input"))
      (node (ref "IC11") (pin "15") (pinfunction "~{ENABLE}_15") (pintype "input"))
      (node (ref "IC11") (pin "16") (pinfunction "LDAC_16") (pintype "input"))
      (node (ref "IC11") (pin "5") (pinfunction "VREFL_5") (pintype "input"))
      (node (ref "IC11") (pin "6") (pinfunction "GND_6") (pintype "power_in"))
      (node (ref "IC12") (pin "6") (pinfunction "~{E}_6") (pintype "input"))
      (node (ref "IC12") (pin "7") (pinfunction "VEE_7") (pintype "power_in"))
      (node (ref "IC12") (pin "8") (pinfunction "GND_8") (pintype "power_in"))
      (node (ref "IC2") (pin "10") (pinfunction "VSS_10") (pintype "power_in"))
      (node (ref "IC2") (pin "15") (pinfunction "A0_15") (pintype "input"))
      (node (ref "IC2") (pin "16") (pinfunction "A1_16") (pintype "input"))
      (node (ref "IC2") (pin "17") (pinfunction "A2_17") (pintype "input"))
      (node (ref "IC3") (pin "10") (pinfunction "+IN_10") (pintype "input"))
      (node (ref "IC3") (pin "11") (pinfunction "V-_11") (pintype "power_in"))
      (node (ref "IC3") (pin "12") (pinfunction "+IN_12") (pintype "input"))
      (node (ref "IC3") (pin "3") (pinfunction "+IN_3") (pintype "input"))
      (node (ref "IC3") (pin "5") (pinfunction "+IN_5") (pintype "input"))
      (node (ref "IC4") (pin "10") (pinfunction "+IN_10") (pintype "input"))
      (node (ref "IC4") (pin "11") (pinfunction "V-_11") (pintype "power_in"))
      (node (ref "IC4") (pin "12") (pinfunction "+IN_12") (pintype "input"))
      (node (ref "IC4") (pin "3") (pinfunction "+IN_3") (pintype "input"))
      (node (ref "IC4") (pin "5") (pinfunction "+IN_5") (pintype "input"))
      (node (ref "IC5") (pin "10") (pinfunction "+IN_10") (pintype "input"))
      (node (ref "IC5") (pin "12") (pinfunction "+IN_12") (pintype "input"))
      (node (ref "IC5") (pin "3") (pinfunction "+IN_3") (pintype "input"))
      (node (ref "IC5") (pin "5") (pinfunction "+IN_5") (pintype "input"))
      (node (ref "IC6") (pin "GND1") (pinfunction "GND1_GND1") (pintype "bidirectional"))
      (node (ref "IC6") (pin "GND3") (pinfunction "GND3_GND3") (pintype "bidirectional"))
      (node (ref "IC6") (pin "GND6") (pinfunction "GND6_GND6") (pintype "bidirectional"))
      (node (ref "IC7") (pin "2") (pinfunction "GND_2") (pintype "passive"))
      (node (ref "IC8") (pin "1") (pinfunction "C_1") (pintype "input"))
      (node (ref "IC9") (pin "2") (pinfunction "GND_2") (pintype "power_in"))
      (node (ref "IC9") (pin "2-2") (pinfunction "GND_2-2") (pintype "power_in"))
    )
    (net (code "53") (name "Net-(0_RX-3)") (class "Default")
      (node (ref "0_RX") (pin "1") (pinfunction "3_1") (pintype "passive"))
      (node (ref "IC6") (pin "0-RX1/CS1/CRX2") (pinfunction "0-RX1/CS1/CRX2_0-RX1/CS1/CRX2") (pintype "bidirectional"))
    )
    (net (code "54") (name "Net-(1_TX-3)") (class "Default")
      (node (ref "1_TX") (pin "1") (pinfunction "3_1") (pintype "passive"))
      (node (ref "IC6") (pin "1-TX1/MISO1/CTX2") (pinfunction "1-TX1/MISO1/CTX2_1-TX1/MISO1/CTX2") (pintype "bidirectional"))
    )
    (net (code "55") (name "Net-(5-3)") (class "Default")
      (node (ref "5") (pin "1") (pinfunction "3_1") (pintype "passive"))
      (node (ref "IC6") (pin "5-IN2") (pinfunction "5-IN2_5-IN2") (pintype "bidirectional"))
    )
    (net (code "56") (name "Net-(18_SDA-3)") (class "Default")
      (node (ref "18_SDA") (pin "1") (pinfunction "3_1") (pintype "passive"))
      (node (ref "IC6") (pin "18-A4/SDA0") (pinfunction "18-A4/SDA0_18-A4/SDA0") (pintype "bidirectional"))
      (node (ref "R115") (pin "1") (pinfunction "1_1") (pintype "passive"))
    )
    (net (code "57") (name "Net-(19_SCL-3)") (class "Default")
      (node (ref "19_SCL") (pin "1") (pinfunction "3_1") (pintype "passive"))
      (node (ref "IC6") (pin "19-A5/SCL0") (pinfunction "19-A5/SCL0_19-A5/SCL0") (pintype "bidirectional"))
      (node (ref "R116") (pin "1") (pinfunction "1_1") (pintype "passive"))
    )
    (net (code "58") (name "Net-(28-3)") (class "Default")
      (node (ref "28") (pin "1") (pinfunction "3_1") (pintype "passive"))
      (node (ref "IC6") (pin "28-RX7") (pinfunction "28-RX7_28-RX7") (pintype "bidirectional"))
    )
    (net (code "59") (name "Net-(29-3)") (class "Default")
      (node (ref "29") (pin "1") (pinfunction "3_1") (pintype "passive"))
      (node (ref "IC6") (pin "29-TX7") (pinfunction "29-TX7_29-TX7") (pintype "bidirectional"))
    )
    (net (code "60") (name "Net-(30-3)") (class "Default")
      (node (ref "30") (pin "1") (pinfunction "3_1") (pintype "passive"))
      (node (ref "IC6") (pin "30-CRX3") (pinfunction "30-CRX3_30-CRX3") (pintype "bidirectional"))
    )
    (net (code "61") (name "Net-(31-3)") (class "Default")
      (node (ref "31") (pin "1") (pinfunction "3_1") (pintype "passive"))
      (node (ref "IC6") (pin "31-CTX3") (pinfunction "31-CTX3_31-CTX3") (pintype "bidirectional"))
    )
    (net (code "62") (name "Net-(32-3)") (class "Default")
      (node (ref "32") (pin "1") (pinfunction "3_1") (pintype "passive"))
      (node (ref "IC6") (pin "32-OUT1B") (pinfunction "32-OUT1B_32-OUT1B") (pintype "bidirectional"))
    )
    (net (code "63") (name "Net-(33-3)") (class "Default")
      (node (ref "33") (pin "1") (pinfunction "3_1") (pintype "passive"))
      (node (ref "IC6") (pin "33-MCLK2") (pinfunction "33-MCLK2_33-MCLK2") (pintype "bidirectional"))
    )
    (net (code "64") (name "Net-(34-3)") (class "Default")
      (node (ref "34") (pin "1") (pinfunction "3_1") (pintype "passive"))
      (node (ref "IC6") (pin "34-RX8") (pinfunction "34-RX8_34-RX8") (pintype "bidirectional"))
    )
    (net (code "65") (name "Net-(35-3)") (class "Default")
      (node (ref "35") (pin "1") (pinfunction "3_1") (pintype "passive"))
      (node (ref "IC6") (pin "35-TX8") (pinfunction "35/TX8_35-TX8") (pintype "bidirectional"))
    )
    (net (code "66") (name "Net-(36-3)") (class "Default")
      (node (ref "36") (pin "1") (pinfunction "3_1") (pintype "passive"))
      (node (ref "IC6") (pin "36-PWM") (pinfunction "36-PWM_36-PWM") (pintype "bidirectional"))
    )
    (net (code "67") (name "Net-(37-3)") (class "Default")
      (node (ref "37") (pin "1") (pinfunction "3_1") (pintype "passive"))
      (node (ref "IC6") (pin "37-PWM") (pinfunction "37-PWM_37-PWM") (pintype "bidirectional"))
    )
    (net (code "68") (name "Net-(38-3)") (class "Default")
      (node (ref "38") (pin "1") (pinfunction "3_1") (pintype "passive"))
      (node (ref "IC6") (pin "38-A14/CS/IN1") (pinfunction "38-A14/CS/IN1_38-A14/CS/IN1") (pintype "bidirectional"))
    )
    (net (code "69") (name "Net-(39-3)") (class "Default")
      (node (ref "39") (pin "1") (pinfunction "3_1") (pintype "passive"))
      (node (ref "IC6") (pin "39-A15/CS/OUT1A") (pinfunction "39-A15/CS/OUT1A_39-A15/CS/OUT1A") (pintype "bidirectional"))
    )
    (net (code "70") (name "Net-(40-3)") (class "Default")
      (node (ref "40") (pin "1") (pinfunction "3_1") (pintype "passive"))
      (node (ref "IC6") (pin "40-A16/CS1") (pinfunction "40-A16/CS1_40-A16/CS1") (pintype "bidirectional"))
    )
    (net (code "71") (name "Net-(41-3)") (class "Default")
      (node (ref "41") (pin "1") (pinfunction "3_1") (pintype "passive"))
      (node (ref "IC6") (pin "41-A17/MISO1") (pinfunction "41-A17/MISO1_41-A17/MISO1") (pintype "bidirectional"))
    )
    (net (code "72") (name "Net-(CV1-3)") (class "Default")
      (node (ref "CV1") (pin "1") (pinfunction "3_1") (pintype "passive"))
      (node (ref "R31") (pin "1") (pinfunction "1_1") (pintype "passive"))
    )
    (net (code "73") (name "Net-(CV1B-3)") (class "Default")
      (node (ref "CV1B") (pin "1") (pinfunction "3_1") (pintype "passive"))
      (node (ref "R32") (pin "1") (pinfunction "1_1") (pintype "passive"))
    )
    (net (code "74") (name "Net-(CV2-3)") (class "Default")
      (node (ref "CV2") (pin "1") (pinfunction "3_1") (pintype "passive"))
      (node (ref "R27") (pin "1") (pinfunction "1_1") (pintype "passive"))
    )
    (net (code "75") (name "Net-(CV2B-3)") (class "Default")
      (node (ref "CV2B") (pin "1") (pinfunction "3_1") (pintype "passive"))
      (node (ref "R28") (pin "1") (pinfunction "1_1") (pintype "passive"))
    )
    (net (code "76") (name "Net-(CV3-3)") (class "Default")
      (node (ref "CV3") (pin "1") (pinfunction "3_1") (pintype "passive"))
      (node (ref "R22") (pin "1") (pinfunction "1_1") (pintype "passive"))
    )
    (net (code "77") (name "Net-(CV3B-3)") (class "Default")
      (node (ref "CV3B") (pin "1") (pinfunction "3_1") (pintype "passive"))
      (node (ref "R23") (pin "1") (pinfunction "1_1") (pintype "passive"))
    )
    (net (code "78") (name "Net-(CV4-3)") (class "Default")
      (node (ref "CV4") (pin "1") (pinfunction "3_1") (pintype "passive"))
      (node (ref "R35") (pin "1") (pinfunction "1_1") (pintype "passive"))
    )
    (net (code "79") (name "Net-(CV4B-3)") (class "Default")
      (node (ref "CV4B") (pin "1") (pinfunction "3_1") (pintype "passive"))
      (node (ref "R36") (pin "1") (pinfunction "1_1") (pintype "passive"))
    )
    (net (code "80") (name "Net-(CV5-3)") (class "Default")
      (node (ref "CV5") (pin "1") (pinfunction "3_1") (pintype "passive"))
      (node (ref "R65") (pin "1") (pinfunction "1_1") (pintype "passive"))
    )
    (net (code "81") (name "Net-(CV5B-3)") (class "Default")
      (node (ref "CV5B") (pin "1") (pinfunction "3_1") (pintype "passive"))
      (node (ref "R66") (pin "1") (pinfunction "1_1") (pintype "passive"))
    )
    (net (code "82") (name "Net-(CV6-3)") (class "Default")
      (node (ref "CV6") (pin "1") (pinfunction "3_1") (pintype "passive"))
      (node (ref "R62") (pin "1") (pinfunction "1_1") (pintype "passive"))
    )
    (net (code "83") (name "Net-(CV6B-3)") (class "Default")
      (node (ref "CV6B") (pin "1") (pinfunction "3_1") (pintype "passive"))
      (node (ref "R63") (pin "1") (pinfunction "1_1") (pintype "passive"))
    )
    (net (code "84") (name "Net-(CV7-3)") (class "Default")
      (node (ref "CV7") (pin "1") (pinfunction "3_1") (pintype "passive"))
      (node (ref "R11") (pin "1") (pinfunction "1_1") (pintype "passive"))
    )
    (net (code "85") (name "Net-(CV7B-3)") (class "Default")
      (node (ref "CV7B") (pin "1") (pinfunction "3_1") (pintype "passive"))
      (node (ref "R12") (pin "1") (pinfunction "1_1") (pintype "passive"))
    )
    (net (code "86") (name "Net-(CV8-3)") (class "Default")
      (node (ref "CV8") (pin "1") (pinfunction "3_1") (pintype "passive"))
      (node (ref "R69") (pin "1") (pinfunction "1_1") (pintype "passive"))
    )
    (net (code "87") (name "Net-(CV8B-3)") (class "Default")
      (node (ref "CV8B") (pin "1") (pinfunction "3_1") (pintype "passive"))
      (node (ref "R70") (pin "1") (pinfunction "1_1") (pintype "passive"))
    )
    (net (code "88") (name "Net-(CVO1-3)") (class "Default")
      (node (ref "CVO1") (pin "1") (pinfunction "3_1") (pintype "passive"))
      (node (ref "R47") (pin "2") (pinfunction "2_2") (pintype "passive"))
    )
    (net (code "89") (name "Net-(CVO2-3)") (class "Default")
      (node (ref "CVO2") (pin "1") (pinfunction "3_1") (pintype "passive"))
      (node (ref "R38") (pin "2") (pinfunction "2_2") (pintype "passive"))
    )
    (net (code "90") (name "Net-(CVO3-3)") (class "Default")
      (node (ref "CVO3") (pin "1") (pinfunction "3_1") (pintype "passive"))
      (node (ref "R41") (pin "2") (pinfunction "2_2") (pintype "passive"))
    )
    (net (code "91") (name "Net-(CVO4-3)") (class "Default")
      (node (ref "CVO4") (pin "1") (pinfunction "3_1") (pintype "passive"))
      (node (ref "R44") (pin "2") (pinfunction "2_2") (pintype "passive"))
    )
    (net (code "92") (name "Net-(CVO5-3)") (class "Default")
      (node (ref "CVO5") (pin "1") (pinfunction "3_1") (pintype "passive"))
      (node (ref "R18") (pin "2") (pinfunction "2_2") (pintype "passive"))
    )
    (net (code "93") (name "Net-(CVO6-3)") (class "Default")
      (node (ref "CVO6") (pin "1") (pinfunction "3_1") (pintype "passive"))
      (node (ref "R3") (pin "2") (pinfunction "2_2") (pintype "passive"))
    )
    (net (code "94") (name "Net-(CVO7-3)") (class "Default")
      (node (ref "CVO7") (pin "1") (pinfunction "3_1") (pintype "passive"))
      (node (ref "R6") (pin "2") (pinfunction "2_2") (pintype "passive"))
    )
    (net (code "95") (name "Net-(CVO8-3)") (class "Default")
      (node (ref "CVO8") (pin "1") (pinfunction "3_1") (pintype "passive"))
      (node (ref "R14") (pin "2") (pinfunction "2_2") (pintype "passive"))
    )
    (net (code "96") (name "Net-(ENC1-3)") (class "Default")
      (node (ref "ENC1") (pin "1") (pinfunction "3_1") (pintype "passive"))
      (node (ref "IC6") (pin "3-LRCLK2") (pinfunction "3-LRCLK2_3-LRCLK2") (pintype "bidirectional"))
    )
    (net (code "97") (name "Net-(ENC2-3)") (class "Default")
      (node (ref "ENC2") (pin "1") (pinfunction "3_1") (pintype "passive"))
      (node (ref "IC6") (pin "4-BCLK2") (pinfunction "4-BCLK2_4-BCLK2") (pintype "bidirectional"))
    )
    (net (code "98") (name "Net-(ENCBTN-3)") (class "Default")
      (node (ref "ENCBTN") (pin "1") (pinfunction "3_1") (pintype "passive"))
      (node (ref "IC6") (pin "2-OUT2") (pinfunction "2-OUT2_2-OUT2") (pintype "bidirectional"))
    )
    (net (code "99") (name "Net-(IC1A--IN)") (class "Default")
      (node (ref "C4") (pin "1") (pinfunction "1_1") (pintype "passive"))
      (node (ref "IC1") (pin "2") (pinfunction "-IN_2") (pintype "input"))
      (node (ref "R1") (pin "1") (pinfunction "1_1") (pintype "passive"))
      (node (ref "R2") (pin "2") (pinfunction "2_2") (pintype "passive"))
      (node (ref "R48") (pin "2") (pinfunction "2_2") (pintype "passive"))
      (node (ref "R83") (pin "2") (pinfunction "2_2") (pintype "passive"))
    )
    (net (code "100") (name "Net-(IC1A-OUT)") (class "Default")
      (node (ref "C4") (pin "2") (pinfunction "2_2") (pintype "passive"))
      (node (ref "IC1") (pin "1") (pinfunction "OUT_1") (pintype "output"))
      (node (ref "R1") (pin "2") (pinfunction "2_2") (pintype "passive"))
      (node (ref "R3") (pin "1") (pinfunction "1_1") (pintype "passive"))
    )
    (net (code "101") (name "Net-(IC1B--IN)") (class "Default")
      (node (ref "C5") (pin "1") (pinfunction "1_1") (pintype "passive"))
      (node (ref "IC1") (pin "6") (pinfunction "-IN_6") (pintype "input"))
      (node (ref "R4") (pin "1") (pinfunction "1_1") (pintype "passive"))
      (node (ref "R49") (pin "2") (pinfunction "2_2") (pintype "passive"))
      (node (ref "R5") (pin "2") (pinfunction "2_2") (pintype "passive"))
      (node (ref "R84") (pin "2") (pinfunction "2_2") (pintype "passive"))
    )
    (net (code "102") (name "Net-(IC1B-OUT)") (class "Default")
      (node (ref "C5") (pin "2") (pinfunction "2_2") (pintype "passive"))
      (node (ref "IC1") (pin "7") (pinfunction "OUT_7") (pintype "output"))
      (node (ref "R4") (pin "2") (pinfunction "2_2") (pintype "passive"))
      (node (ref "R6") (pin "1") (pinfunction "1_1") (pintype "passive"))
    )
    (net (code "103") (name "Net-(IC1C--IN)") (class "Default")
      (node (ref "C8") (pin "1") (pinfunction "1_1") (pintype "passive"))
      (node (ref "IC1") (pin "9") (pinfunction "-IN_9") (pintype "input"))
      (node (ref "R10") (pin "2") (pinfunction "2_2") (pintype "passive"))
      (node (ref "R50") (pin "2") (pinfunction "2_2") (pintype "passive"))
      (node (ref "R85") (pin "2") (pinfunction "2_2") (pintype "passive"))
      (node (ref "R9") (pin "1") (pinfunction "1_1") (pintype "passive"))
    )
    (net (code "104") (name "Net-(IC1C-OUT)") (class "Default")
      (node (ref "C8") (pin "2") (pinfunction "2_2") (pintype "passive"))
      (node (ref "IC1") (pin "8") (pinfunction "OUT_8") (pintype "output"))
      (node (ref "R14") (pin "1") (pinfunction "1_1") (pintype "passive"))
      (node (ref "R9") (pin "2") (pinfunction "2_2") (pintype "passive"))
    )
    (net (code "105") (name "Net-(IC1D--IN)") (class "Default")
      (node (ref "C9") (pin "1") (pinfunction "1_1") (pintype "passive"))
      (node (ref "IC1") (pin "13") (pinfunction "-IN_13") (pintype "input"))
      (node (ref "R16") (pin "1") (pinfunction "1_1") (pintype "passive"))
      (node (ref "R17") (pin "2") (pinfunction "2_2") (pintype "passive"))
      (node (ref "R51") (pin "2") (pinfunction "2_2") (pintype "passive"))
      (node (ref "R86") (pin "2") (pinfunction "2_2") (pintype "passive"))
    )
    (net (code "106") (name "Net-(IC1D-OUT)") (class "Default")
      (node (ref "C9") (pin "2") (pinfunction "2_2") (pintype "passive"))
      (node (ref "IC1") (pin "14") (pinfunction "OUT_14") (pintype "output"))
      (node (ref "R16") (pin "2") (pinfunction "2_2") (pintype "passive"))
      (node (ref "R18") (pin "1") (pinfunction "1_1") (pintype "passive"))
    )
    (net (code "107") (name "Net-(IC2-~{RESET})") (class "Default")
      (node (ref "IC2") (pin "18") (pinfunction "~{RESET}_18") (pintype "input"))
      (node (ref "R82") (pin "2") (pinfunction "2_2") (pintype "passive"))
    )
    (net (code "108") (name "Net-(IC3A--IN)") (class "Default")
      (node (ref "C7") (pin "1") (pinfunction "1_1") (pintype "passive"))
      (node (ref "IC3") (pin "2") (pinfunction "-IN_2") (pintype "input"))
      (node (ref "R11") (pin "2") (pinfunction "2_2") (pintype "passive"))
      (node (ref "R12") (pin "2") (pinfunction "2_2") (pintype "passive"))
      (node (ref "R13") (pin "2") (pinfunction "2_2") (pintype "passive"))
      (node (ref "R8") (pin "1") (pinfunction "1_1") (pintype "passive"))
    )
    (net (code "109") (name "Net-(IC3B--IN)") (class "Default")
      (node (ref "C10") (pin "1") (pinfunction "1_1") (pintype "passive"))
      (node (ref "IC3") (pin "6") (pinfunction "-IN_6") (pintype "input"))
      (node (ref "R15") (pin "1") (pinfunction "1_1") (pintype "passive"))
      (node (ref "R29") (pin "2") (pinfunction "2_2") (pintype "passive"))
      (node (ref "R62") (pin "2") (pinfunction "2_2") (pintype "passive"))
      (node (ref "R63") (pin "2") (pinfunction "2_2") (pintype "passive"))
    )
    (net (code "110") (name "Net-(IC3C--IN)") (class "Default")
      (node (ref "C11") (pin "1") (pinfunction "1_1") (pintype "passive"))
      (node (ref "IC3") (pin "9") (pinfunction "-IN_9") (pintype "input"))
      (node (ref "R64") (pin "1") (pinfunction "1_1") (pintype "passive"))
      (node (ref "R65") (pin "2") (pinfunction "2_2") (pintype "passive"))
      (node (ref "R66") (pin "2") (pinfunction "2_2") (pintype "passive"))
      (node (ref "R67") (pin "2") (pinfunction "2_2") (pintype "passive"))
    )
    (net (code "111") (name "Net-(IC3D--IN)") (class "Default")
      (node (ref "C14") (pin "1") (pinfunction "1_1") (pintype "passive"))
      (node (ref "IC3") (pin "13") (pinfunction "-IN_13") (pintype "input"))
      (node (ref "R68") (pin "1") (pinfunction "1_1") (pintype "passive"))
      (node (ref "R69") (pin "2") (pinfunction "2_2") (pintype "passive"))
      (node (ref "R70") (pin "2") (pinfunction "2_2") (pintype "passive"))
      (node (ref "R71") (pin "2") (pinfunction "2_2") (pintype "passive"))
    )
    (net (code "112") (name "Net-(IC4A--IN)") (class "Default")
      (node (ref "C16") (pin "1") (pinfunction "1_1") (pintype "passive"))
      (node (ref "IC4") (pin "2") (pinfunction "-IN_2") (pintype "input"))
      (node (ref "R21") (pin "1") (pinfunction "1_1") (pintype "passive"))
      (node (ref "R22") (pin "2") (pinfunction "2_2") (pintype "passive"))
      (node (ref "R23") (pin "2") (pinfunction "2_2") (pintype "passive"))
      (node (ref "R24") (pin "2") (pinfunction "2_2") (pintype "passive"))
    )
    (net (code "113") (name "Net-(IC4B--IN)") (class "Default")
      (node (ref "C17") (pin "1") (pinfunction "1_1") (pintype "passive"))
      (node (ref "IC4") (pin "6") (pinfunction "-IN_6") (pintype "input"))
      (node (ref "R25") (pin "1") (pinfunction "1_1") (pintype "passive"))
      (node (ref "R26") (pin "2") (pinfunction "2_2") (pintype "passive"))
      (node (ref "R27") (pin "2") (pinfunction "2_2") (pintype "passive"))
      (node (ref "R28") (pin "2") (pinfunction "2_2") (pintype "passive"))
    )
    (net (code "114") (name "Net-(IC4C--IN)") (class "Default")
      (node (ref "C20") (pin "1") (pinfunction "1_1") (pintype "passive"))
      (node (ref "IC4") (pin "9") (pinfunction "-IN_9") (pintype "input"))
      (node (ref "R30") (pin "1") (pinfunction "1_1") (pintype "passive"))
      (node (ref "R31") (pin "2") (pinfunction "2_2") (pintype "passive"))
      (node (ref "R32") (pin "2") (pinfunction "2_2") (pintype "passive"))
      (node (ref "R33") (pin "2") (pinfunction "2_2") (pintype "passive"))
    )
    (net (code "115") (name "Net-(IC4D--IN)") (class "Default")
      (node (ref "C21") (pin "1") (pinfunction "1_1") (pintype "passive"))
      (node (ref "IC4") (pin "13") (pinfunction "-IN_13") (pintype "input"))
      (node (ref "R34") (pin "1") (pinfunction "1_1") (pintype "passive"))
      (node (ref "R35") (pin "2") (pinfunction "2_2") (pintype "passive"))
      (node (ref "R36") (pin "2") (pinfunction "2_2") (pintype "passive"))
      (node (ref "R37") (pin "2") (pinfunction "2_2") (pintype "passive"))
    )
    (net (code "116") (name "Net-(IC5A--IN)") (class "Default")
      (node (ref "C12") (pin "1") (pinfunction "1_1") (pintype "passive"))
      (node (ref "IC5") (pin "2") (pinfunction "-IN_2") (pintype "input"))
      (node (ref "R19") (pin "1") (pinfunction "1_1") (pintype "passive"))
      (node (ref "R20") (pin "2") (pinfunction "2_2") (pintype "passive"))
      (node (ref "R52") (pin "2") (pinfunction "2_2") (pintype "passive"))
      (node (ref "R90") (pin "2") (pinfunction "2_2") (pintype "passive"))
    )
    (net (code "117") (name "Net-(IC5A-OUT)") (class "Default")
      (node (ref "C12") (pin "2") (pinfunction "2_2") (pintype "passive"))
      (node (ref "IC5") (pin "1") (pinfunction "OUT_1") (pintype "output"))
      (node (ref "R19") (pin "2") (pinfunction "2_2") (pintype "passive"))
      (node (ref "R38") (pin "1") (pinfunction "1_1") (pintype "passive"))
    )
    (net (code "118") (name "Net-(IC5B--IN)") (class "Default")
      (node (ref "C13") (pin "1") (pinfunction "1_1") (pintype "passive"))
      (node (ref "IC5") (pin "6") (pinfunction "-IN_6") (pintype "input"))
      (node (ref "R39") (pin "1") (pinfunction "1_1") (pintype "passive"))
      (node (ref "R40") (pin "2") (pinfunction "2_2") (pintype "passive"))
      (node (ref "R53") (pin "2") (pinfunction "2_2") (pintype "passive"))
      (node (ref "R89") (pin "2") (pinfunction "2_2") (pintype "passive"))
    )
    (net (code "119") (name "Net-(IC5B-OUT)") (class "Default")
      (node (ref "C13") (pin "2") (pinfunction "2_2") (pintype "passive"))
      (node (ref "IC5") (pin "7") (pinfunction "OUT_7") (pintype "output"))
      (node (ref "R39") (pin "2") (pinfunction "2_2") (pintype "passive"))
      (node (ref "R41") (pin "1") (pinfunction "1_1") (pintype "passive"))
    )
    (net (code "120") (name "Net-(IC5C--IN)") (class "Default")
      (node (ref "C19") (pin "1") (pinfunction "1_1") (pintype "passive"))
      (node (ref "IC5") (pin "9") (pinfunction "-IN_9") (pintype "input"))
      (node (ref "R42") (pin "1") (pinfunction "1_1") (pintype "passive"))
      (node (ref "R43") (pin "2") (pinfunction "2_2") (pintype "passive"))
      (node (ref "R54") (pin "2") (pinfunction "2_2") (pintype "passive"))
      (node (ref "R88") (pin "2") (pinfunction "2_2") (pintype "passive"))
    )
    (net (code "121") (name "Net-(IC5C-OUT)") (class "Default")
      (node (ref "C19") (pin "2") (pinfunction "2_2") (pintype "passive"))
      (node (ref "IC5") (pin "8") (pinfunction "OUT_8") (pintype "output"))
      (node (ref "R42") (pin "2") (pinfunction "2_2") (pintype "passive"))
      (node (ref "R44") (pin "1") (pinfunction "1_1") (pintype "passive"))
    )
    (net (code "122") (name "Net-(IC5D--IN)") (class "Default")
      (node (ref "C22") (pin "1") (pinfunction "1_1") (pintype "passive"))
      (node (ref "IC5") (pin "13") (pinfunction "-IN_13") (pintype "input"))
      (node (ref "R45") (pin "1") (pinfunction "1_1") (pintype "passive"))
      (node (ref "R46") (pin "2") (pinfunction "2_2") (pintype "passive"))
      (node (ref "R55") (pin "2") (pinfunction "2_2") (pintype "passive"))
      (node (ref "R87") (pin "2") (pinfunction "2_2") (pintype "passive"))
    )
    (net (code "123") (name "Net-(IC5D-OUT)") (class "Default")
      (node (ref "C22") (pin "2") (pinfunction "2_2") (pintype "passive"))
      (node (ref "IC5") (pin "14") (pinfunction "OUT_14") (pintype "output"))
      (node (ref "R45") (pin "2") (pinfunction "2_2") (pintype "passive"))
      (node (ref "R47") (pin "1") (pinfunction "1_1") (pintype "passive"))
    )
    (net (code "124") (name "Net-(IC7-VI)") (class "Default")
      (node (ref "C28") (pin "2") (pinfunction "2_2") (pintype "passive"))
      (node (ref "IC7") (pin "1") (pinfunction "VI_1") (pintype "input"))
      (node (ref "L1") (pin "2") (pinfunction "2_2") (pintype "passive"))
    )
    (net (code "125") (name "Net-(IC9-VIN)") (class "Default")
      (node (ref "C29") (pin "2") (pinfunction "2_2") (pintype "passive"))
      (node (ref "IC9") (pin "3") (pinfunction "VIN_3") (pintype "power_in"))
      (node (ref "L2") (pin "2") (pinfunction "2_2") (pintype "passive"))
    )
    (net (code "126") (name "Net-(IC10-VREFH{slash}VREFOUT)") (class "Default")
      (node (ref "C34") (pin "1") (pinfunction "1_1") (pintype "passive"))
      (node (ref "IC10") (pin "3") (pinfunction "VREFH/VREFOUT_3") (pintype "bidirectional"))
    )
    (net (code "127") (name "Net-(IC11-VREFH{slash}VREFOUT)") (class "Default")
      (node (ref "C33") (pin "1") (pinfunction "1_1") (pintype "passive"))
      (node (ref "IC11") (pin "3") (pinfunction "VREFH/VREFOUT_3") (pintype "bidirectional"))
    )
    (net (code "128") (name "Net-(IC12-Y0)") (class "Default")
      (node (ref "IC12") (pin "13") (pinfunction "Y0_13") (pintype "bidirectional"))
      (node (ref "PT2") (pin "1") (pinfunction "3_1") (pintype "passive"))
      (node (ref "R93") (pin "1") (pinfunction "1_1") (pintype "passive"))
    )
    (net (code "129") (name "Net-(IC12-Y1)") (class "Default")
      (node (ref "IC12") (pin "14") (pinfunction "Y1_14") (pintype "bidirectional"))
      (node (ref "PT3") (pin "1") (pinfunction "3_1") (pintype "passive"))
      (node (ref "R92") (pin "1") (pinfunction "1_1") (pintype "passive"))
    )
    (net (code "130") (name "Net-(IC12-Y2)") (class "Default")
      (node (ref "IC12") (pin "15") (pinfunction "Y2_15") (pintype "bidirectional"))
      (node (ref "PT4") (pin "1") (pinfunction "3_1") (pintype "passive"))
      (node (ref "R91") (pin "1") (pinfunction "1_1") (pintype "passive"))
    )
    (net (code "131") (name "Net-(IC12-Y3)") (class "Default")
      (node (ref "IC12") (pin "12") (pinfunction "Y3_12") (pintype "bidirectional"))
      (node (ref "PT1") (pin "1") (pinfunction "3_1") (pintype "passive"))
      (node (ref "R94") (pin "1") (pinfunction "1_1") (pintype "passive"))
    )
    (net (code "132") (name "Net-(IC12-Y4)") (class "Default")
      (node (ref "IC12") (pin "1") (pinfunction "Y4_1") (pintype "bidirectional"))
      (node (ref "PT5") (pin "1") (pinfunction "3_1") (pintype "passive"))
    )
    (net (code "133") (name "Net-(IC12-Y5)") (class "Default")
      (node (ref "IC12") (pin "5") (pinfunction "Y5_5") (pintype "bidirectional"))
      (node (ref "PT8") (pin "1") (pinfunction "3_1") (pintype "passive"))
    )
    (net (code "134") (name "Net-(IC12-Y6)") (class "Default")
      (node (ref "IC12") (pin "2") (pinfunction "Y6_2") (pintype "bidirectional"))
      (node (ref "PT6") (pin "1") (pinfunction "3_1") (pintype "passive"))
    )
    (net (code "135") (name "Net-(IC12-Y7)") (class "Default")
      (node (ref "IC12") (pin "4") (pinfunction "Y7_4") (pintype "bidirectional"))
      (node (ref "PT7") (pin "1") (pinfunction "3_1") (pintype "passive"))
    )
    (net (code "136") (name "Net-(IO1-3)") (class "Default")
      (node (ref "IO1") (pin "1") (pinfunction "3_1") (pintype "passive"))
      (node (ref "Q9") (pin "3") (pinfunction "D_3") (pintype "passive"))
      (node (ref "R100") (pin "1") (pinfunction "1_1") (pintype "passive"))
    )
    (net (code "137") (name "Net-(IO2-3)") (class "Default")
      (node (ref "IO2") (pin "1") (pinfunction "3_1") (pintype "passive"))
      (node (ref "Q10") (pin "3") (pinfunction "D_3") (pintype "passive"))
      (node (ref "R102") (pin "1") (pinfunction "1_1") (pintype "passive"))
    )
    (net (code "138") (name "Net-(IO3-3)") (class "Default")
      (node (ref "IO3") (pin "1") (pinfunction "3_1") (pintype "passive"))
      (node (ref "Q11") (pin "3") (pinfunction "D_3") (pintype "passive"))
      (node (ref "R104") (pin "1") (pinfunction "1_1") (pintype "passive"))
    )
    (net (code "139") (name "Net-(IO4-3)") (class "Default")
      (node (ref "IO4") (pin "1") (pinfunction "3_1") (pintype "passive"))
      (node (ref "Q12") (pin "3") (pinfunction "D_3") (pintype "passive"))
      (node (ref "R106") (pin "1") (pinfunction "1_1") (pintype "passive"))
    )
    (net (code "140") (name "Net-(IO5-3)") (class "Default")
      (node (ref "IO5") (pin "1") (pinfunction "3_1") (pintype "passive"))
      (node (ref "Q13") (pin "3") (pinfunction "D_3") (pintype "passive"))
      (node (ref "R108") (pin "1") (pinfunction "1_1") (pintype "passive"))
    )
    (net (code "141") (name "Net-(IO6-3)") (class "Default")
      (node (ref "IO6") (pin "1") (pinfunction "3_1") (pintype "passive"))
      (node (ref "Q14") (pin "3") (pinfunction "D_3") (pintype "passive"))
      (node (ref "R110") (pin "1") (pinfunction "1_1") (pintype "passive"))
    )
    (net (code "142") (name "Net-(IO7-3)") (class "Default")
      (node (ref "IO7") (pin "1") (pinfunction "3_1") (pintype "passive"))
      (node (ref "Q15") (pin "3") (pinfunction "D_3") (pintype "passive"))
      (node (ref "R112") (pin "1") (pinfunction "1_1") (pintype "passive"))
    )
    (net (code "143") (name "Net-(IO8-3)") (class "Default")
      (node (ref "IO8") (pin "1") (pinfunction "3_1") (pintype "passive"))
      (node (ref "Q16") (pin "3") (pinfunction "D_3") (pintype "passive"))
      (node (ref "R114") (pin "1") (pinfunction "1_1") (pintype "passive"))
    )
    (net (code "144") (name "Net-(IO9-3)") (class "Default")
      (node (ref "IO9") (pin "1") (pinfunction "3_1") (pintype "passive"))
      (node (ref "Q1") (pin "3") (pinfunction "D_3") (pintype "passive"))
      (node (ref "R99") (pin "1") (pinfunction "1_1") (pintype "passive"))
    )
    (net (code "145") (name "Net-(IO10-3)") (class "Default")
      (node (ref "IO10") (pin "1") (pinfunction "3_1") (pintype "passive"))
      (node (ref "Q2") (pin "3") (pinfunction "D_3") (pintype "passive"))
      (node (ref "R58") (pin "1") (pinfunction "1_1") (pintype "passive"))
    )
    (net (code "146") (name "Net-(IO11-3)") (class "Default")
      (node (ref "IO11") (pin "1") (pinfunction "3_1") (pintype "passive"))
      (node (ref "Q3") (pin "3") (pinfunction "D_3") (pintype "passive"))
      (node (ref "R60") (pin "1") (pinfunction "1_1") (pintype "passive"))
    )
    (net (code "147") (name "Net-(IO12-3)") (class "Default")
      (node (ref "IO12") (pin "1") (pinfunction "3_1") (pintype "passive"))
      (node (ref "Q4") (pin "3") (pinfunction "D_3") (pintype "passive"))
      (node (ref "R72") (pin "1") (pinfunction "1_1") (pintype "passive"))
    )
    (net (code "148") (name "Net-(IO13-3)") (class "Default")
      (node (ref "IO13") (pin "1") (pinfunction "3_1") (pintype "passive"))
      (node (ref "Q5") (pin "3") (pinfunction "D_3") (pintype "passive"))
      (node (ref "R74") (pin "1") (pinfunction "1_1") (pintype "passive"))
    )
    (net (code "149") (name "Net-(IO14-3)") (class "Default")
      (node (ref "IO14") (pin "1") (pinfunction "3_1") (pintype "passive"))
      (node (ref "Q6") (pin "3") (pinfunction "D_3") (pintype "passive"))
      (node (ref "R76") (pin "1") (pinfunction "1_1") (pintype "passive"))
    )
    (net (code "150") (name "Net-(IO15-3)") (class "Default")
      (node (ref "IO15") (pin "1") (pinfunction "3_1") (pintype "passive"))
      (node (ref "Q7") (pin "3") (pinfunction "D_3") (pintype "passive"))
      (node (ref "R78") (pin "1") (pinfunction "1_1") (pintype "passive"))
    )
    (net (code "151") (name "Net-(IO16-3)") (class "Default")
      (node (ref "IO16") (pin "1") (pinfunction "3_1") (pintype "passive"))
      (node (ref "Q8") (pin "3") (pinfunction "D_3") (pintype "passive"))
      (node (ref "R80") (pin "1") (pinfunction "1_1") (pintype "passive"))
    )
    (net (code "152") (name "unconnected-(IC6-Pad3V3-1)") (class "Default")
      (node (ref "IC6") (pin "3V3-1") (pinfunction "3V3-1_3V3-1") (pintype "bidirectional"))
    )
    (net (code "153") (name "unconnected-(P1-3-Pad1)") (class "Default")
      (node (ref "P1") (pin "1") (pinfunction "3_1") (pintype "passive"))
    )
    (net (code "154") (name "unconnected-(P2-3-Pad1)") (class "Default")
      (node (ref "P2") (pin "1") (pinfunction "3_1") (pintype "passive"))
    )
    (net (code "155") (name "unconnected-(P3-3-Pad1)") (class "Default")
      (node (ref "P3") (pin "1") (pinfunction "3_1") (pintype "passive"))
    )
    (net (code "156") (name "unconnected-(P4-3-Pad1)") (class "Default")
      (node (ref "P4") (pin "1") (pinfunction "3_1") (pintype "passive"))
    )
    (net (code "157") (name "unconnected-(P5-3-Pad1)") (class "Default")
      (node (ref "P5") (pin "1") (pinfunction "3_1") (pintype "passive"))
    )
    (net (code "158") (name "unconnected-(P6-3-Pad1)") (class "Default")
      (node (ref "P6") (pin "1") (pinfunction "3_1") (pintype "passive"))
    )
    (net (code "159") (name "unconnected-(P7-3-Pad1)") (class "Default")
      (node (ref "P7") (pin "1") (pinfunction "3_1") (pintype "passive"))
    )
    (net (code "160") (name "unconnected-(P8-3-Pad1)") (class "Default")
      (node (ref "P8") (pin "1") (pinfunction "3_1") (pintype "passive"))
    )
    (net (code "161") (name "unconnected-(P9-3-Pad1)") (class "Default")
      (node (ref "P9") (pin "1") (pinfunction "3_1") (pintype "passive"))
    )
    (net (code "162") (name "unconnected-(P10-3-Pad1)") (class "Default")
      (node (ref "P10") (pin "1") (pinfunction "3_1") (pintype "passive"))
    )
    (net (code "163") (name "unconnected-(P11-3-Pad1)") (class "Default")
      (node (ref "P11") (pin "1") (pinfunction "3_1") (pintype "passive"))
    )
    (net (code "164") (name "unconnected-(P12-3-Pad1)") (class "Default")
      (node (ref "P12") (pin "1") (pinfunction "3_1") (pintype "passive"))
    )
    (net (code "165") (name "unconnected-(P13-3-Pad1)") (class "Default")
      (node (ref "P13") (pin "1") (pinfunction "3_1") (pintype "passive"))
    )
    (net (code "166") (name "unconnected-(P14-3-Pad1)") (class "Default")
      (node (ref "P14") (pin "1") (pinfunction "3_1") (pintype "passive"))
    )
    (net (code "167") (name "unconnected-(P15-3-Pad1)") (class "Default")
      (node (ref "P15") (pin "1") (pinfunction "3_1") (pintype "passive"))
    )
    (net (code "168") (name "unconnected-(P16-3-Pad1)") (class "Default")
      (node (ref "P16") (pin "1") (pinfunction "3_1") (pintype "passive"))
    )
    (net (code "169") (name "unconnected-(P17-3-Pad1)") (class "Default")
      (node (ref "P17") (pin "1") (pinfunction "3_1") (pintype "passive"))
    )
    (net (code "170") (name "unconnected-(P18-3-Pad1)") (class "Default")
      (node (ref "P18") (pin "1") (pinfunction "3_1") (pintype "passive"))
    )
    (net (code "171") (name "unconnected-(P19-3-Pad1)") (class "Default")
      (node (ref "P19") (pin "1") (pinfunction "3_1") (pintype "passive"))
    )
    (net (code "172") (name "unconnected-(P21-3-Pad1)") (class "Default")
      (node (ref "P21") (pin "1") (pinfunction "3_1") (pintype "passive"))
    )
    (net (code "173") (name "unconnected-(P22-3-Pad1)") (class "Default")
      (node (ref "P22") (pin "1") (pinfunction "3_1") (pintype "passive"))
    )
    (net (code "174") (name "unconnected-(P23-3-Pad1)") (class "Default")
      (node (ref "P23") (pin "1") (pinfunction "3_1") (pintype "passive"))
    )
    (net (code "175") (name "unconnected-(P24-3-Pad1)") (class "Default")
      (node (ref "P24") (pin "1") (pinfunction "3_1") (pintype "passive"))
    )
    (net (code "176") (name "unconnected-(P25-3-Pad1)") (class "Default")
      (node (ref "P25") (pin "1") (pinfunction "3_1") (pintype "passive"))
    )
    (net (code "177") (name "unconnected-(P26-3-Pad1)") (class "Default")
      (node (ref "P26") (pin "1") (pinfunction "3_1") (pintype "passive"))
    )
    (net (code "178") (name "unconnected-(P27-3-Pad1)") (class "Default")
      (node (ref "P27") (pin "1") (pinfunction "3_1") (pintype "passive"))
    )
    (net (code "179") (name "unconnected-(P28-3-Pad1)") (class "Default")
      (node (ref "P28") (pin "1") (pinfunction "3_1") (pintype "passive"))
    )
    (net (code "180") (name "unconnected-(P29-3-Pad1)") (class "Default")
      (node (ref "P29") (pin "1") (pinfunction "3_1") (pintype "passive"))
    )
    (net (code "181") (name "unconnected-(P30-3-Pad1)") (class "Default")
      (node (ref "P30") (pin "1") (pinfunction "3_1") (pintype "passive"))
    )
    (net (code "182") (name "unconnected-(P31-3-Pad1)") (class "Default")
      (node (ref "P31") (pin "1") (pinfunction "3_1") (pintype "passive"))
    )
    (net (code "183") (name "unconnected-(P32-3-Pad1)") (class "Default")
      (node (ref "P32") (pin "1") (pinfunction "3_1") (pintype "passive"))
    )
    (net (code "184") (name "unconnected-(P33-3-Pad1)") (class "Default")
      (node (ref "P33") (pin "1") (pinfunction "3_1") (pintype "passive"))
    )
    (net (code "185") (name "unconnected-(P34-3-Pad1)") (class "Default")
      (node (ref "P34") (pin "1") (pinfunction "3_1") (pintype "passive"))
    )
    (net (code "186") (name "unconnected-(P35-3-Pad1)") (class "Default")
      (node (ref "P35") (pin "1") (pinfunction "3_1") (pintype "passive"))
    )
    (net (code "187") (name "unconnected-(P36-3-Pad1)") (class "Default")
      (node (ref "P36") (pin "1") (pinfunction "3_1") (pintype "passive"))
    )
    (net (code "188") (name "unconnected-(P37-3-Pad1)") (class "Default")
      (node (ref "P37") (pin "1") (pinfunction "3_1") (pintype "passive"))
    )
    (net (code "189") (name "unconnected-(P38-3-Pad1)") (class "Default")
      (node (ref "P38") (pin "1") (pinfunction "3_1") (pintype "passive"))
    )
    (net (code "190") (name "unconnected-(P39-3-Pad1)") (class "Default")
      (node (ref "P39") (pin "1") (pinfunction "3_1") (pintype "passive"))
    )
    (net (code "191") (name "unconnected-(P40-3-Pad1)") (class "Default")
      (node (ref "P40") (pin "1") (pinfunction "3_1") (pintype "passive"))
    )
    (net (code "192") (name "unconnected-(P41-3-Pad1)") (class "Default")
      (node (ref "P41") (pin "1") (pinfunction "3_1") (pintype "passive"))
    )
    (net (code "193") (name "unconnected-(P42-3-Pad1)") (class "Default")
      (node (ref "P42") (pin "1") (pinfunction "3_1") (pintype "passive"))
    )
    (net (code "194") (name "unconnected-(P44-3-Pad1)") (class "Default")
      (node (ref "P44") (pin "1") (pinfunction "3_1") (pintype "passive"))
    )
    (net (code "195") (name "unconnected-(P45-3-Pad1)") (class "Default")
      (node (ref "P45") (pin "1") (pinfunction "3_1") (pintype "passive"))
    )
    (net (code "196") (name "unconnected-(P46-3-Pad1)") (class "Default")
      (node (ref "P46") (pin "1") (pinfunction "3_1") (pintype "passive"))
    )
    (net (code "197") (name "unconnected-(P47-3-Pad1)") (class "Default")
      (node (ref "P47") (pin "1") (pinfunction "3_1") (pintype "passive"))
    )
    (net (code "198") (name "unconnected-(P49-3-Pad1)") (class "Default")
      (node (ref "P49") (pin "1") (pinfunction "3_1") (pintype "passive"))
    )
    (net (code "199") (name "unconnected-(P50-3-Pad1)") (class "Default")
      (node (ref "P50") (pin "1") (pinfunction "3_1") (pintype "passive"))
    )
  )
)
